# guhPLC_dimmModule_V0_1.net
KiCad netlist of a schematic drawn in EAGLE
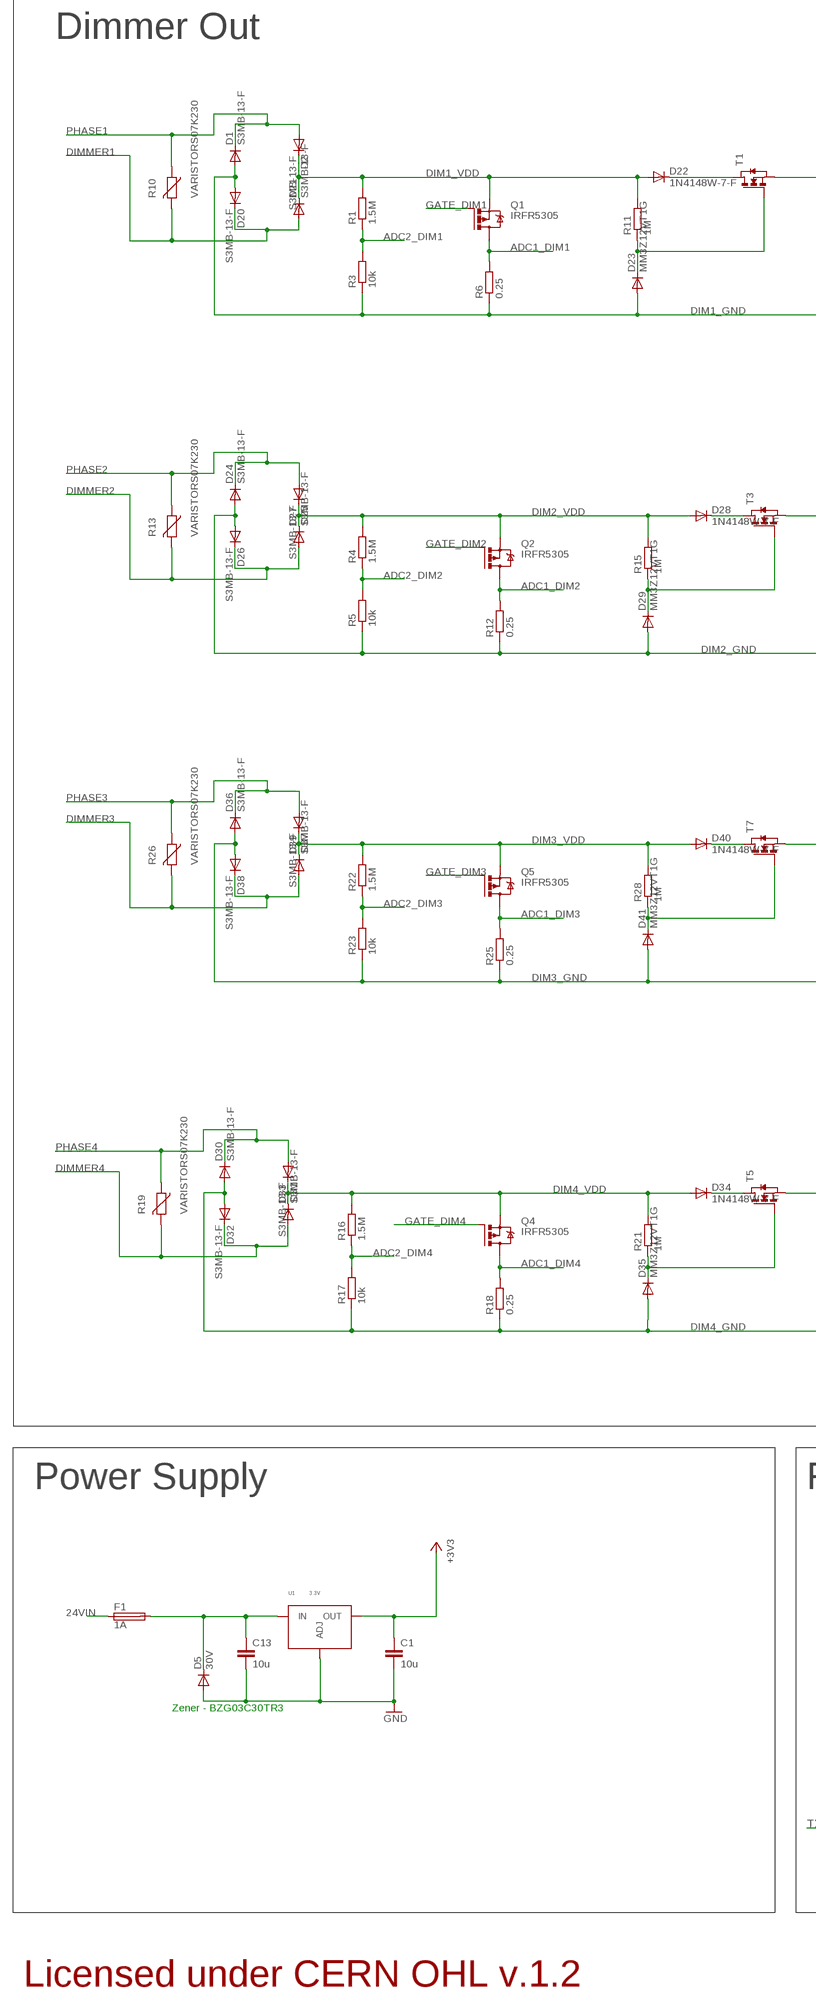
[diagram p0: schematic, sheet 1, part 1 of 2]
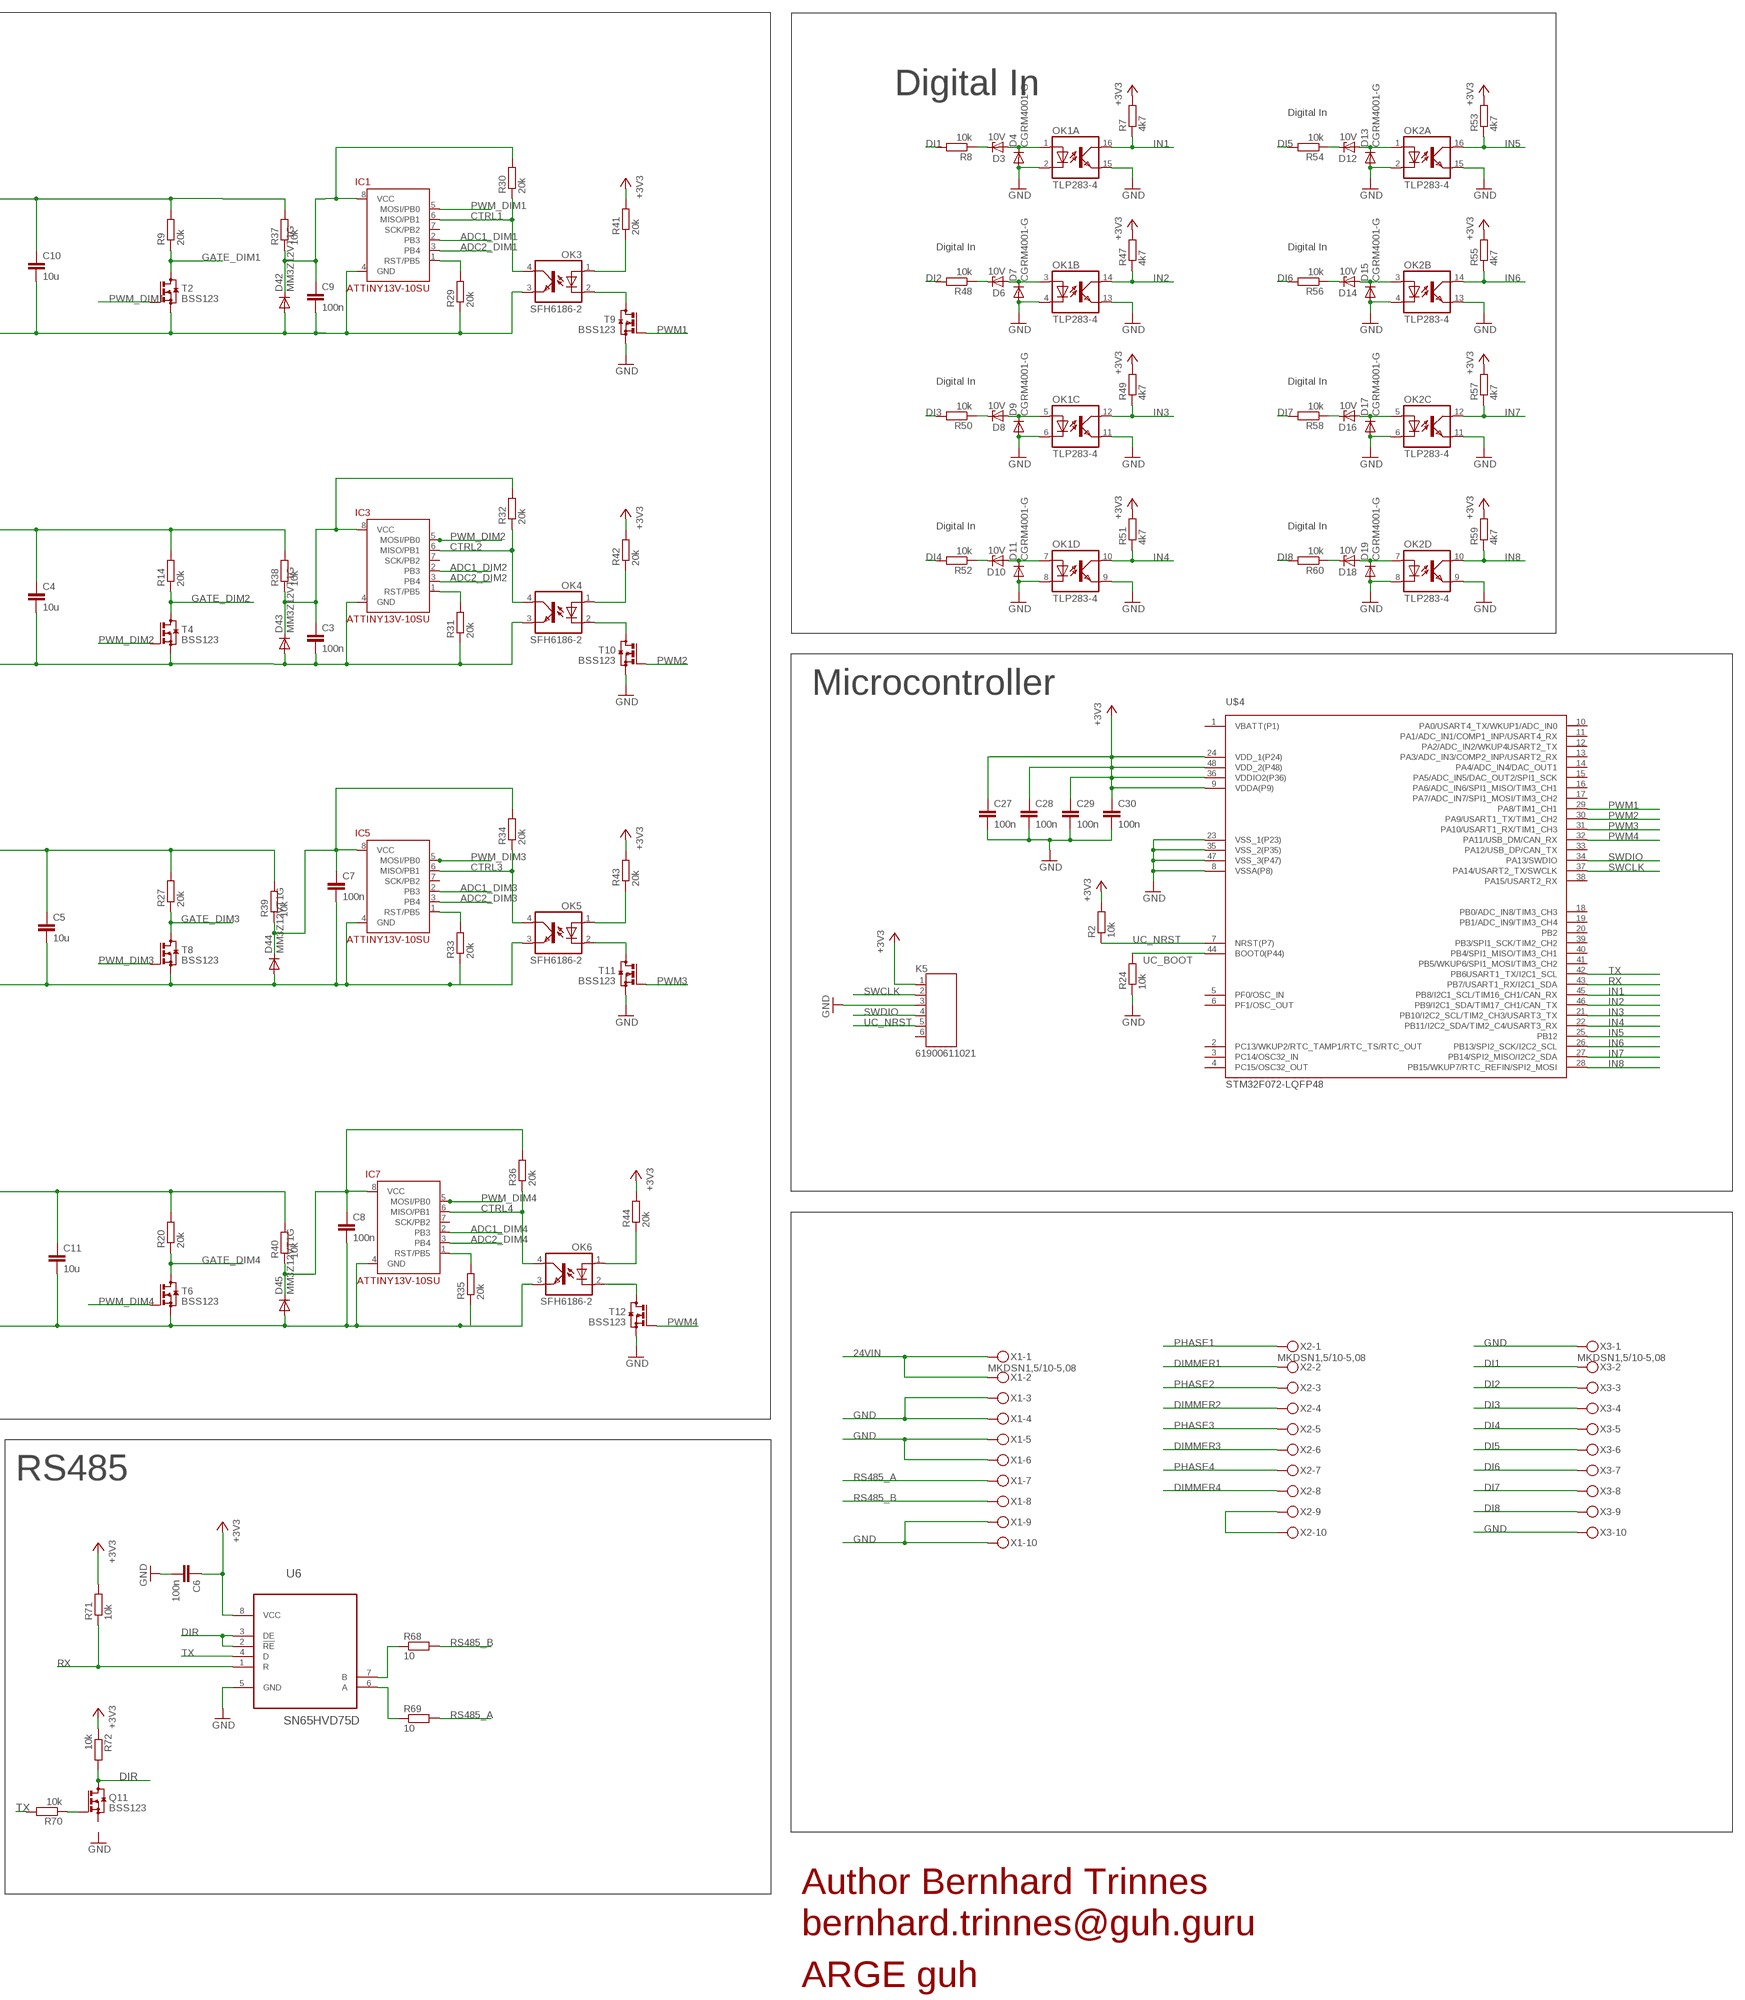
[diagram p1: schematic, sheet 1, part 2 of 2]

(export (version "E")
  (design (tool "Eeschema 10.0.6"))
  (components
    (comp (ref "C1")
      (value "10u")
      (footprint "eagle-import:C1206")
      (libsource (lib "eagle-import") (part "C-EUC1206"))
    )
    (comp (ref "C3")
      (value "100n")
      (footprint "eagle-import:C0603")
      (libsource (lib "eagle-import") (part "C-EUC0603"))
    )
    (comp (ref "C4")
      (value "10u")
      (footprint "eagle-import:C1206")
      (libsource (lib "eagle-import") (part "C-EUC1206"))
    )
    (comp (ref "C5")
      (value "10u")
      (footprint "eagle-import:C1206")
      (libsource (lib "eagle-import") (part "C-EUC1206"))
    )
    (comp (ref "C6")
      (value "100n")
      (footprint "eagle-import:C1206")
      (libsource (lib "eagle-import") (part "C-EUC1206"))
    )
    (comp (ref "C7")
      (value "100n")
      (footprint "eagle-import:C0603")
      (libsource (lib "eagle-import") (part "C-EUC0603"))
    )
    (comp (ref "C8")
      (value "100n")
      (footprint "eagle-import:C0603")
      (libsource (lib "eagle-import") (part "C-EUC0603"))
    )
    (comp (ref "C9")
      (value "100n")
      (footprint "eagle-import:C0603")
      (libsource (lib "eagle-import") (part "C-EUC0603"))
    )
    (comp (ref "C10")
      (value "10u")
      (footprint "eagle-import:C1206")
      (libsource (lib "eagle-import") (part "C-EUC1206"))
    )
    (comp (ref "C11")
      (value "10u")
      (footprint "eagle-import:C1206")
      (libsource (lib "eagle-import") (part "C-EUC1206"))
    )
    (comp (ref "C13")
      (value "10u")
      (footprint "eagle-import:C1206")
      (libsource (lib "eagle-import") (part "C-EUC1206"))
    )
    (comp (ref "C27")
      (value "100n")
      (footprint "eagle-import:C0603")
      (libsource (lib "eagle-import") (part "C-EUC0603"))
    )
    (comp (ref "C28")
      (value "100n")
      (footprint "eagle-import:C0603")
      (libsource (lib "eagle-import") (part "C-EUC0603"))
    )
    (comp (ref "C29")
      (value "100n")
      (footprint "eagle-import:C0603")
      (libsource (lib "eagle-import") (part "C-EUC0603"))
    )
    (comp (ref "C30")
      (value "100n")
      (footprint "eagle-import:C0603")
      (libsource (lib "eagle-import") (part "C-EUC0603"))
    )
    (comp (ref "D1")
      (value "S3MB-13-F")
      (footprint "eagle-import:DO214AA")
      (libsource (lib "eagle-import") (part "DIODE-DO214AA"))
    )
    (comp (ref "D2")
      (value "S3MB-13-F")
      (footprint "eagle-import:DO214AA")
      (libsource (lib "eagle-import") (part "DIODE-DO214AA"))
    )
    (comp (ref "D3")
      (value "10V")
      (footprint "eagle-import:SOD80C")
      (libsource (lib "eagle-import") (part "ZENER-DIODESOD80C"))
    )
    (comp (ref "D4")
      (value "CGRM4001-G")
      (footprint "eagle-import:SOD-123_MINI-SMA")
      (libsource (lib "eagle-import") (part "CGRM400-G1"))
    )
    (comp (ref "D5")
      (value "30V")
      (footprint "eagle-import:DO214AC")
      (libsource (lib "eagle-import") (part "DIODE-DO214AC"))
    )
    (comp (ref "D6")
      (value "10V")
      (footprint "eagle-import:SOD80C")
      (libsource (lib "eagle-import") (part "ZENER-DIODESOD80C"))
    )
    (comp (ref "D7")
      (value "CGRM4001-G")
      (footprint "eagle-import:SOD-123_MINI-SMA")
      (libsource (lib "eagle-import") (part "CGRM400-G1"))
    )
    (comp (ref "D8")
      (value "10V")
      (footprint "eagle-import:SOD80C")
      (libsource (lib "eagle-import") (part "ZENER-DIODESOD80C"))
    )
    (comp (ref "D9")
      (value "CGRM4001-G")
      (footprint "eagle-import:SOD-123_MINI-SMA")
      (libsource (lib "eagle-import") (part "CGRM400-G1"))
    )
    (comp (ref "D10")
      (value "10V")
      (footprint "eagle-import:SOD80C")
      (libsource (lib "eagle-import") (part "ZENER-DIODESOD80C"))
    )
    (comp (ref "D11")
      (value "CGRM4001-G")
      (footprint "eagle-import:SOD-123_MINI-SMA")
      (libsource (lib "eagle-import") (part "CGRM400-G1"))
    )
    (comp (ref "D12")
      (value "10V")
      (footprint "eagle-import:SOD80C")
      (libsource (lib "eagle-import") (part "ZENER-DIODESOD80C"))
    )
    (comp (ref "D13")
      (value "CGRM4001-G")
      (footprint "eagle-import:SOD-123_MINI-SMA")
      (libsource (lib "eagle-import") (part "CGRM400-G1"))
    )
    (comp (ref "D14")
      (value "10V")
      (footprint "eagle-import:SOD80C")
      (libsource (lib "eagle-import") (part "ZENER-DIODESOD80C"))
    )
    (comp (ref "D15")
      (value "CGRM4001-G")
      (footprint "eagle-import:SOD-123_MINI-SMA")
      (libsource (lib "eagle-import") (part "CGRM400-G1"))
    )
    (comp (ref "D16")
      (value "10V")
      (footprint "eagle-import:SOD80C")
      (libsource (lib "eagle-import") (part "ZENER-DIODESOD80C"))
    )
    (comp (ref "D17")
      (value "CGRM4001-G")
      (footprint "eagle-import:SOD-123_MINI-SMA")
      (libsource (lib "eagle-import") (part "CGRM400-G1"))
    )
    (comp (ref "D18")
      (value "10V")
      (footprint "eagle-import:SOD80C")
      (libsource (lib "eagle-import") (part "ZENER-DIODESOD80C"))
    )
    (comp (ref "D19")
      (value "CGRM4001-G")
      (footprint "eagle-import:SOD-123_MINI-SMA")
      (libsource (lib "eagle-import") (part "CGRM400-G1"))
    )
    (comp (ref "D20")
      (value "S3MB-13-F")
      (footprint "eagle-import:DO214AA")
      (libsource (lib "eagle-import") (part "DIODE-DO214AA"))
    )
    (comp (ref "D21")
      (value "S3MB-13-F")
      (footprint "eagle-import:DO214AA")
      (libsource (lib "eagle-import") (part "DIODE-DO214AA"))
    )
    (comp (ref "D22")
      (value "1N4148W-7-F")
      (footprint "eagle-import:SOD123")
      (libsource (lib "eagle-import") (part "DIODE-SOD123"))
    )
    (comp (ref "D23")
      (value "MM3Z12VT1G")
      (footprint "eagle-import:SOD323-W")
      (libsource (lib "eagle-import") (part "DIODE-SOD323-W"))
    )
    (comp (ref "D24")
      (value "S3MB-13-F")
      (footprint "eagle-import:DO214AA")
      (libsource (lib "eagle-import") (part "DIODE-DO214AA"))
    )
    (comp (ref "D25")
      (value "S3MB-13-F")
      (footprint "eagle-import:DO214AA")
      (libsource (lib "eagle-import") (part "DIODE-DO214AA"))
    )
    (comp (ref "D26")
      (value "S3MB-13-F")
      (footprint "eagle-import:DO214AA")
      (libsource (lib "eagle-import") (part "DIODE-DO214AA"))
    )
    (comp (ref "D27")
      (value "S3MB-13-F")
      (footprint "eagle-import:DO214AA")
      (libsource (lib "eagle-import") (part "DIODE-DO214AA"))
    )
    (comp (ref "D28")
      (value "1N4148W-7-F")
      (footprint "eagle-import:SOD123")
      (libsource (lib "eagle-import") (part "DIODE-SOD123"))
    )
    (comp (ref "D29")
      (value "MM3Z12VT1G")
      (footprint "eagle-import:SOD323-W")
      (libsource (lib "eagle-import") (part "guh_DIODE-SOD323-W"))
    )
    (comp (ref "D30")
      (value "S3MB-13-F")
      (footprint "eagle-import:DO214AA")
      (libsource (lib "eagle-import") (part "DIODE-DO214AA"))
    )
    (comp (ref "D31")
      (value "S3MB-13-F")
      (footprint "eagle-import:DO214AA")
      (libsource (lib "eagle-import") (part "DIODE-DO214AA"))
    )
    (comp (ref "D32")
      (value "S3MB-13-F")
      (footprint "eagle-import:DO214AA")
      (libsource (lib "eagle-import") (part "DIODE-DO214AA"))
    )
    (comp (ref "D33")
      (value "S3MB-13-F")
      (footprint "eagle-import:DO214AA")
      (libsource (lib "eagle-import") (part "DIODE-DO214AA"))
    )
    (comp (ref "D34")
      (value "1N4148W-7-F")
      (footprint "eagle-import:SOD123")
      (libsource (lib "eagle-import") (part "DIODE-SOD123"))
    )
    (comp (ref "D35")
      (value "MM3Z12VT1G")
      (footprint "eagle-import:SOD323-W")
      (libsource (lib "eagle-import") (part "guh_DIODE-SOD323-W"))
    )
    (comp (ref "D36")
      (value "S3MB-13-F")
      (footprint "eagle-import:DO214AA")
      (libsource (lib "eagle-import") (part "DIODE-DO214AA"))
    )
    (comp (ref "D37")
      (value "S3MB-13-F")
      (footprint "eagle-import:DO214AA")
      (libsource (lib "eagle-import") (part "DIODE-DO214AA"))
    )
    (comp (ref "D38")
      (value "S3MB-13-F")
      (footprint "eagle-import:DO214AA")
      (libsource (lib "eagle-import") (part "DIODE-DO214AA"))
    )
    (comp (ref "D39")
      (value "S3MB-13-F")
      (footprint "eagle-import:DO214AA")
      (libsource (lib "eagle-import") (part "DIODE-DO214AA"))
    )
    (comp (ref "D40")
      (value "1N4148W-7-F")
      (footprint "eagle-import:SOD123")
      (libsource (lib "eagle-import") (part "DIODE-SOD123"))
    )
    (comp (ref "D41")
      (value "MM3Z12VT1G")
      (footprint "eagle-import:SOD323-W")
      (libsource (lib "eagle-import") (part "guh_DIODE-SOD323-W"))
    )
    (comp (ref "D42")
      (value "MM3Z12VT1G")
      (footprint "eagle-import:SOD323-W")
      (libsource (lib "eagle-import") (part "DIODE-SOD323-W"))
    )
    (comp (ref "D43")
      (value "MM3Z12VT1G")
      (footprint "eagle-import:SOD323-W")
      (libsource (lib "eagle-import") (part "DIODE-SOD323-W"))
    )
    (comp (ref "D44")
      (value "MM3Z12VT1G")
      (footprint "eagle-import:SOD323-W")
      (libsource (lib "eagle-import") (part "DIODE-SOD323-W"))
    )
    (comp (ref "D45")
      (value "MM3Z12VT1G")
      (footprint "eagle-import:SOD323-W")
      (libsource (lib "eagle-import") (part "DIODE-SOD323-W"))
    )
    (comp (ref "F1")
      (value "1A")
      (footprint "eagle-import:LITTLEFUSE")
      (libsource (lib "eagle-import") (part "LITTLEFUSE"))
    )
    (comp (ref "IC1")
      (value "ATTINY13V-10SU")
      (footprint "eagle-import:SOIC8")
      (libsource (lib "eagle-import") (part "ATTINY13V-10SU"))
    )
    (comp (ref "IC3")
      (value "ATTINY13V-10SU")
      (footprint "eagle-import:SOIC8")
      (libsource (lib "eagle-import") (part "ATTINY13V-10SU"))
    )
    (comp (ref "IC5")
      (value "ATTINY13V-10SU")
      (footprint "eagle-import:SOIC8")
      (libsource (lib "eagle-import") (part "ATTINY13V-10SU"))
    )
    (comp (ref "IC7")
      (value "ATTINY13V-10SU")
      (footprint "eagle-import:SOIC8")
      (libsource (lib "eagle-import") (part "ATTINY13V-10SU"))
    )
    (comp (ref "K5")
      (value "61900611021")
      (footprint "eagle-import:61900611021")
      (libsource (lib "eagle-import") (part "61900611021"))
    )
    (comp (ref "OK1")
      (value "TLP283-4")
      (footprint "eagle-import:MINI-FLAT-16")
      (libsource (lib "eagle-import") (part "TLP283-4"))
    )
    (comp (ref "OK2")
      (value "TLP283-4")
      (footprint "eagle-import:MINI-FLAT-16")
      (libsource (lib "eagle-import") (part "TLP283-4"))
    )
    (comp (ref "OK3")
      (value "SFH6186-2")
      (footprint "eagle-import:SMD4")
      (fields (field (name "MF") "VISHAY/TELEFUNKEN"))
      (libsource (lib "eagle-import") (part "SFH618?6-2"))
    )
    (comp (ref "OK4")
      (value "SFH6186-2")
      (footprint "eagle-import:SMD4")
      (fields (field (name "MF") "VISHAY/TELEFUNKEN"))
      (libsource (lib "eagle-import") (part "SFH618?6-2"))
    )
    (comp (ref "OK5")
      (value "SFH6186-2")
      (footprint "eagle-import:SMD4")
      (fields (field (name "MF") "VISHAY/TELEFUNKEN"))
      (libsource (lib "eagle-import") (part "SFH618?6-2"))
    )
    (comp (ref "OK6")
      (value "SFH6186-2")
      (footprint "eagle-import:SMD4")
      (fields (field (name "MF") "VISHAY/TELEFUNKEN"))
      (libsource (lib "eagle-import") (part "SFH618?6-2"))
    )
    (comp (ref "Q1")
      (value "IRFR5305")
      (footprint "eagle-import:D-PAK_TO252AA")
      (libsource (lib "eagle-import") (part "IRF?5305R"))
    )
    (comp (ref "Q2")
      (value "IRFR5305")
      (footprint "eagle-import:D-PAK_TO252AA")
      (libsource (lib "eagle-import") (part "IRF?5305R"))
    )
    (comp (ref "Q4")
      (value "IRFR5305")
      (footprint "eagle-import:D-PAK_TO252AA")
      (libsource (lib "eagle-import") (part "IRF?5305R"))
    )
    (comp (ref "Q5")
      (value "IRFR5305")
      (footprint "eagle-import:D-PAK_TO252AA")
      (libsource (lib "eagle-import") (part "IRF?5305R"))
    )
    (comp (ref "Q11")
      (value "BSS123")
      (footprint "eagle-import:SOT23")
      (libsource (lib "eagle-import") (part "BSS123"))
    )
    (comp (ref "R1")
      (value "1.5M")
      (footprint "eagle-import:R1206")
      (libsource (lib "eagle-import") (part "R-EU_R1206"))
    )
    (comp (ref "R2")
      (value "10k")
      (footprint "eagle-import:R0603")
      (libsource (lib "eagle-import") (part "R-EU_R0603"))
    )
    (comp (ref "R3")
      (value "10k")
      (footprint "eagle-import:R1206")
      (libsource (lib "eagle-import") (part "R-EU_R1206"))
    )
    (comp (ref "R4")
      (value "1.5M")
      (footprint "eagle-import:M1206")
      (libsource (lib "eagle-import") (part "R-EU_M1206"))
    )
    (comp (ref "R5")
      (value "10k")
      (footprint "eagle-import:M1206")
      (libsource (lib "eagle-import") (part "R-EU_M1206"))
    )
    (comp (ref "R6")
      (value "0.25")
      (footprint "eagle-import:R1206")
      (libsource (lib "eagle-import") (part "R-EU_R1206"))
    )
    (comp (ref "R7")
      (value "4k7")
      (footprint "eagle-import:R0603")
      (libsource (lib "eagle-import") (part "R-EU_R0603"))
    )
    (comp (ref "R8")
      (value "10k")
      (footprint "eagle-import:R0805")
      (libsource (lib "eagle-import") (part "R-EU_R0805"))
    )
    (comp (ref "R9")
      (value "20k")
      (footprint "eagle-import:M1206")
      (libsource (lib "eagle-import") (part "R-EU_M1206"))
    )
    (comp (ref "R10")
      (value "VARISTORS07K230")
      (footprint "eagle-import:S07K230")
      (libsource (lib "eagle-import") (part "VARISTORS07K230"))
    )
    (comp (ref "R11")
      (value "1M")
      (footprint "eagle-import:R1206")
      (libsource (lib "eagle-import") (part "R-EU_R1206"))
    )
    (comp (ref "R12")
      (value "0.25")
      (footprint "eagle-import:M1206")
      (libsource (lib "eagle-import") (part "R-EU_M1206"))
    )
    (comp (ref "R13")
      (value "VARISTORS07K230")
      (footprint "eagle-import:S07K230")
      (libsource (lib "eagle-import") (part "VARISTORS07K230"))
    )
    (comp (ref "R14")
      (value "20k")
      (footprint "eagle-import:M1206")
      (libsource (lib "eagle-import") (part "R-EU_M1206"))
    )
    (comp (ref "R15")
      (value "1M")
      (footprint "eagle-import:M1206")
      (libsource (lib "eagle-import") (part "R-EU_M1206"))
    )
    (comp (ref "R16")
      (value "1.5M")
      (footprint "eagle-import:M1206")
      (libsource (lib "eagle-import") (part "R-EU_M1206"))
    )
    (comp (ref "R17")
      (value "10k")
      (footprint "eagle-import:M1206")
      (libsource (lib "eagle-import") (part "R-EU_M1206"))
    )
    (comp (ref "R18")
      (value "0.25")
      (footprint "eagle-import:M1206")
      (libsource (lib "eagle-import") (part "R-EU_M1206"))
    )
    (comp (ref "R19")
      (value "VARISTORS07K230")
      (footprint "eagle-import:S07K230")
      (libsource (lib "eagle-import") (part "VARISTORS07K230"))
    )
    (comp (ref "R20")
      (value "20k")
      (footprint "eagle-import:M1206")
      (libsource (lib "eagle-import") (part "R-EU_M1206"))
    )
    (comp (ref "R21")
      (value "1M")
      (footprint "eagle-import:M1206")
      (libsource (lib "eagle-import") (part "R-EU_M1206"))
    )
    (comp (ref "R22")
      (value "1.5M")
      (footprint "eagle-import:M1206")
      (libsource (lib "eagle-import") (part "R-EU_M1206"))
    )
    (comp (ref "R23")
      (value "10k")
      (footprint "eagle-import:M1206")
      (libsource (lib "eagle-import") (part "R-EU_M1206"))
    )
    (comp (ref "R24")
      (value "10k")
      (footprint "eagle-import:R0603")
      (libsource (lib "eagle-import") (part "R-EU_R0603"))
    )
    (comp (ref "R25")
      (value "0.25")
      (footprint "eagle-import:M1206")
      (libsource (lib "eagle-import") (part "R-EU_M1206"))
    )
    (comp (ref "R26")
      (value "VARISTORS07K230")
      (footprint "eagle-import:S07K230")
      (libsource (lib "eagle-import") (part "VARISTORS07K230"))
    )
    (comp (ref "R27")
      (value "20k")
      (footprint "eagle-import:M1206")
      (libsource (lib "eagle-import") (part "R-EU_M1206"))
    )
    (comp (ref "R28")
      (value "1M")
      (footprint "eagle-import:M1206")
      (libsource (lib "eagle-import") (part "R-EU_M1206"))
    )
    (comp (ref "R29")
      (value "20k")
      (footprint "eagle-import:R0603")
      (libsource (lib "eagle-import") (part "R-EU_R0603"))
    )
    (comp (ref "R30")
      (value "20k")
      (footprint "eagle-import:R0603")
      (libsource (lib "eagle-import") (part "R-EU_R0603"))
    )
    (comp (ref "R31")
      (value "20k")
      (footprint "eagle-import:R0603")
      (libsource (lib "eagle-import") (part "R-EU_R0603"))
    )
    (comp (ref "R32")
      (value "20k")
      (footprint "eagle-import:R0603")
      (libsource (lib "eagle-import") (part "R-EU_R0603"))
    )
    (comp (ref "R33")
      (value "20k")
      (footprint "eagle-import:R0603")
      (libsource (lib "eagle-import") (part "R-EU_R0603"))
    )
    (comp (ref "R34")
      (value "20k")
      (footprint "eagle-import:R0603")
      (libsource (lib "eagle-import") (part "R-EU_R0603"))
    )
    (comp (ref "R35")
      (value "20k")
      (footprint "eagle-import:R0603")
      (libsource (lib "eagle-import") (part "R-EU_R0603"))
    )
    (comp (ref "R36")
      (value "20k")
      (footprint "eagle-import:R0603")
      (libsource (lib "eagle-import") (part "R-EU_R0603"))
    )
    (comp (ref "R37")
      (value "10k")
      (footprint "eagle-import:M1206")
      (libsource (lib "eagle-import") (part "R-EU_M1206"))
    )
    (comp (ref "R38")
      (value "10k")
      (footprint "eagle-import:M1206")
      (libsource (lib "eagle-import") (part "R-EU_M1206"))
    )
    (comp (ref "R39")
      (value "10k")
      (footprint "eagle-import:M1206")
      (libsource (lib "eagle-import") (part "R-EU_M1206"))
    )
    (comp (ref "R40")
      (value "10k")
      (footprint "eagle-import:M1206")
      (libsource (lib "eagle-import") (part "R-EU_M1206"))
    )
    (comp (ref "R41")
      (value "20k")
      (footprint "eagle-import:R0603")
      (libsource (lib "eagle-import") (part "R-EU_R0603"))
    )
    (comp (ref "R42")
      (value "20k")
      (footprint "eagle-import:R0603")
      (libsource (lib "eagle-import") (part "R-EU_R0603"))
    )
    (comp (ref "R43")
      (value "20k")
      (footprint "eagle-import:R0603")
      (libsource (lib "eagle-import") (part "R-EU_R0603"))
    )
    (comp (ref "R44")
      (value "20k")
      (footprint "eagle-import:R0603")
      (libsource (lib "eagle-import") (part "R-EU_R0603"))
    )
    (comp (ref "R47")
      (value "4k7")
      (footprint "eagle-import:R0603")
      (libsource (lib "eagle-import") (part "R-EU_R0603"))
    )
    (comp (ref "R48")
      (value "10k")
      (footprint "eagle-import:R0805")
      (libsource (lib "eagle-import") (part "R-EU_R0805"))
    )
    (comp (ref "R49")
      (value "4k7")
      (footprint "eagle-import:R0603")
      (libsource (lib "eagle-import") (part "R-EU_R0603"))
    )
    (comp (ref "R50")
      (value "10k")
      (footprint "eagle-import:R0805")
      (libsource (lib "eagle-import") (part "R-EU_R0805"))
    )
    (comp (ref "R51")
      (value "4k7")
      (footprint "eagle-import:R0603")
      (libsource (lib "eagle-import") (part "R-EU_R0603"))
    )
    (comp (ref "R52")
      (value "10k")
      (footprint "eagle-import:R0805")
      (libsource (lib "eagle-import") (part "R-EU_R0805"))
    )
    (comp (ref "R53")
      (value "4k7")
      (footprint "eagle-import:R0603")
      (libsource (lib "eagle-import") (part "R-EU_R0603"))
    )
    (comp (ref "R54")
      (value "10k")
      (footprint "eagle-import:R0805")
      (libsource (lib "eagle-import") (part "R-EU_R0805"))
    )
    (comp (ref "R55")
      (value "4k7")
      (footprint "eagle-import:R0603")
      (libsource (lib "eagle-import") (part "R-EU_R0603"))
    )
    (comp (ref "R56")
      (value "10k")
      (footprint "eagle-import:R0805")
      (libsource (lib "eagle-import") (part "R-EU_R0805"))
    )
    (comp (ref "R57")
      (value "4k7")
      (footprint "eagle-import:R0603")
      (libsource (lib "eagle-import") (part "R-EU_R0603"))
    )
    (comp (ref "R58")
      (value "10k")
      (footprint "eagle-import:R0805")
      (libsource (lib "eagle-import") (part "R-EU_R0805"))
    )
    (comp (ref "R59")
      (value "4k7")
      (footprint "eagle-import:R0603")
      (libsource (lib "eagle-import") (part "R-EU_R0603"))
    )
    (comp (ref "R60")
      (value "10k")
      (footprint "eagle-import:R0805")
      (libsource (lib "eagle-import") (part "R-EU_R0805"))
    )
    (comp (ref "R68")
      (value "10")
      (footprint "eagle-import:R0603")
      (libsource (lib "eagle-import") (part "R-EU_R0603"))
    )
    (comp (ref "R69")
      (value "10")
      (footprint "eagle-import:R0603")
      (libsource (lib "eagle-import") (part "R-EU_R0603"))
    )
    (comp (ref "R70")
      (value "10k")
      (footprint "eagle-import:R0603")
      (libsource (lib "eagle-import") (part "R-EU_R0603"))
    )
    (comp (ref "R71")
      (value "10k")
      (footprint "eagle-import:R0603")
      (libsource (lib "eagle-import") (part "R-EU_R0603"))
    )
    (comp (ref "R72")
      (value "10k")
      (footprint "eagle-import:R0603")
      (libsource (lib "eagle-import") (part "R-EU_R0603"))
    )
    (comp (ref "T1")
      (value "NMOSSOT23")
      (footprint "eagle-import:SOT-23")
      (libsource (lib "eagle-import") (part "NMOSSOT23"))
    )
    (comp (ref "T2")
      (value "BSS123")
      (footprint "eagle-import:SOT23")
      (libsource (lib "eagle-import") (part "BSS123"))
    )
    (comp (ref "T3")
      (value "NMOSSOT23")
      (footprint "eagle-import:SOT-23")
      (libsource (lib "eagle-import") (part "NMOSSOT23"))
    )
    (comp (ref "T4")
      (value "BSS123")
      (footprint "eagle-import:SOT23")
      (libsource (lib "eagle-import") (part "BSS123"))
    )
    (comp (ref "T5")
      (value "NMOSSOT23")
      (footprint "eagle-import:SOT-23")
      (libsource (lib "eagle-import") (part "NMOSSOT23"))
    )
    (comp (ref "T6")
      (value "BSS123")
      (footprint "eagle-import:SOT23")
      (libsource (lib "eagle-import") (part "BSS123"))
    )
    (comp (ref "T7")
      (value "NMOSSOT23")
      (footprint "eagle-import:SOT-23")
      (libsource (lib "eagle-import") (part "NMOSSOT23"))
    )
    (comp (ref "T8")
      (value "BSS123")
      (footprint "eagle-import:SOT23")
      (libsource (lib "eagle-import") (part "BSS123"))
    )
    (comp (ref "T9")
      (value "BSS123")
      (footprint "eagle-import:SOT23")
      (libsource (lib "eagle-import") (part "BSS123"))
    )
    (comp (ref "T10")
      (value "BSS123")
      (footprint "eagle-import:SOT23")
      (libsource (lib "eagle-import") (part "BSS123"))
    )
    (comp (ref "T11")
      (value "BSS123")
      (footprint "eagle-import:SOT23")
      (libsource (lib "eagle-import") (part "BSS123"))
    )
    (comp (ref "T12")
      (value "BSS123")
      (footprint "eagle-import:SOT23")
      (libsource (lib "eagle-import") (part "BSS123"))
    )
    (comp (ref "U$4")
      (value "STM32F072-LQFP48")
      (footprint "eagle-import:LQFP48")
      (libsource (lib "eagle-import") (part "STM32F072-LQFP48"))
    )
    (comp (ref "U1")
      (value "3.3V")
      (footprint "eagle-import:TO-252-3L")
      (libsource (lib "eagle-import") (part "ADJ_VOLTAGE_REGTO-252-3L"))
    )
    (comp (ref "U6")
      (value "SN65HVD75D")
      (footprint "eagle-import:SOIC127P600X175-8N")
      (libsource (lib "eagle-import") (part "SN65HVD75D"))
    )
    (comp (ref "X1")
      (value "MKDSN1,5/10-5,08")
      (footprint "eagle-import:MKDSN1,5_10-5,08")
      (fields (field (name "MPN") "SMKDSN1,5/10-5,08"))
      (libsource (lib "eagle-import") (part "MKDSN1,5/10-5,08"))
    )
    (comp (ref "X2")
      (value "MKDSN1,5/10-5,08")
      (footprint "eagle-import:MKDSN1,5_10-5,08")
      (fields (field (name "MPN") "SMKDSN1,5/10-5,08"))
      (libsource (lib "eagle-import") (part "MKDSN1,5/10-5,08"))
    )
    (comp (ref "X3")
      (value "MKDSN1,5/10-5,08")
      (footprint "eagle-import:MKDSN1,5_10-5,08")
      (fields (field (name "MPN") "SMKDSN1,5/10-5,08"))
      (libsource (lib "eagle-import") (part "MKDSN1,5/10-5,08"))
    )
  )
  (nets
    (net (code "1") (name "+3V3") (class "Default")
      (node (ref "C1") (pin "1") (pinfunction "1_1") (pintype "passive"))
      (node (ref "C27") (pin "1") (pinfunction "1_1") (pintype "passive"))
      (node (ref "C28") (pin "1") (pinfunction "1_1") (pintype "passive"))
      (node (ref "C29") (pin "1") (pinfunction "1_1") (pintype "passive"))
      (node (ref "C30") (pin "1") (pinfunction "1_1") (pintype "passive"))
      (node (ref "C6") (pin "1") (pinfunction "1_1") (pintype "passive"))
      (node (ref "K5") (pin "1") (pinfunction "1_1") (pintype "passive"))
      (node (ref "R2") (pin "2") (pinfunction "2_2") (pintype "passive"))
      (node (ref "R41") (pin "2") (pinfunction "2_2") (pintype "passive"))
      (node (ref "R42") (pin "2") (pinfunction "2_2") (pintype "passive"))
      (node (ref "R43") (pin "2") (pinfunction "2_2") (pintype "passive"))
      (node (ref "R44") (pin "2") (pinfunction "2_2") (pintype "passive"))
      (node (ref "R47") (pin "2") (pinfunction "2_2") (pintype "passive"))
      (node (ref "R49") (pin "2") (pinfunction "2_2") (pintype "passive"))
      (node (ref "R51") (pin "2") (pinfunction "2_2") (pintype "passive"))
      (node (ref "R53") (pin "2") (pinfunction "2_2") (pintype "passive"))
      (node (ref "R55") (pin "2") (pinfunction "2_2") (pintype "passive"))
      (node (ref "R57") (pin "2") (pinfunction "2_2") (pintype "passive"))
      (node (ref "R59") (pin "2") (pinfunction "2_2") (pintype "passive"))
      (node (ref "R7") (pin "2") (pinfunction "2_2") (pintype "passive"))
      (node (ref "R71") (pin "2") (pinfunction "2_2") (pintype "passive"))
      (node (ref "R72") (pin "1") (pinfunction "1_1") (pintype "passive"))
      (node (ref "U$4") (pin "24") (pinfunction "VDD_1(P24)_24") (pintype "bidirectional"))
      (node (ref "U$4") (pin "36") (pinfunction "VDDIO2(P36)_36") (pintype "bidirectional"))
      (node (ref "U$4") (pin "48") (pinfunction "VDD_2(P48)_48") (pintype "bidirectional"))
      (node (ref "U$4") (pin "9") (pinfunction "VDDA(P9)_9") (pintype "bidirectional"))
      (node (ref "U1") (pin "PAD") (pinfunction "OUT_PAD") (pintype "bidirectional"))
      (node (ref "U6") (pin "8") (pinfunction "VCC_8") (pintype "power_in"))
    )
    (net (code "2") (name "/24VIN") (class "Default")
      (node (ref "F1") (pin "1") (pinfunction "1_1") (pintype "passive"))
      (node (ref "X1") (pin "1") (pinfunction "KL_1") (pintype "passive"))
      (node (ref "X1") (pin "2") (pinfunction "KL_2") (pintype "passive"))
    )
    (net (code "3") (name "/ADC1_DIM1") (class "Default")
      (node (ref "IC1") (pin "2") (pinfunction "PB3_2") (pintype "bidirectional"))
      (node (ref "Q1") (pin "4") (pinfunction "D_4") (pintype "passive"))
      (node (ref "R6") (pin "2") (pinfunction "2_2") (pintype "passive"))
    )
    (net (code "4") (name "/ADC1_DIM2") (class "Default")
      (node (ref "IC3") (pin "2") (pinfunction "PB3_2") (pintype "bidirectional"))
      (node (ref "Q2") (pin "4") (pinfunction "D_4") (pintype "passive"))
      (node (ref "R12") (pin "2") (pinfunction "2_2") (pintype "passive"))
    )
    (net (code "5") (name "/ADC1_DIM3") (class "Default")
      (node (ref "IC5") (pin "2") (pinfunction "PB3_2") (pintype "bidirectional"))
      (node (ref "Q5") (pin "4") (pinfunction "D_4") (pintype "passive"))
      (node (ref "R25") (pin "2") (pinfunction "2_2") (pintype "passive"))
    )
    (net (code "6") (name "/ADC1_DIM4") (class "Default")
      (node (ref "IC7") (pin "2") (pinfunction "PB3_2") (pintype "bidirectional"))
      (node (ref "Q4") (pin "4") (pinfunction "D_4") (pintype "passive"))
      (node (ref "R18") (pin "2") (pinfunction "2_2") (pintype "passive"))
    )
    (net (code "7") (name "/ADC2_DIM1") (class "Default")
      (node (ref "IC1") (pin "3") (pinfunction "PB4_3") (pintype "bidirectional"))
      (node (ref "R1") (pin "1") (pinfunction "1_1") (pintype "passive"))
      (node (ref "R3") (pin "2") (pinfunction "2_2") (pintype "passive"))
    )
    (net (code "8") (name "/ADC2_DIM2") (class "Default")
      (node (ref "IC3") (pin "3") (pinfunction "PB4_3") (pintype "bidirectional"))
      (node (ref "R4") (pin "1") (pinfunction "1_1") (pintype "passive"))
      (node (ref "R5") (pin "2") (pinfunction "2_2") (pintype "passive"))
    )
    (net (code "9") (name "/ADC2_DIM3") (class "Default")
      (node (ref "IC5") (pin "3") (pinfunction "PB4_3") (pintype "bidirectional"))
      (node (ref "R22") (pin "1") (pinfunction "1_1") (pintype "passive"))
      (node (ref "R23") (pin "2") (pinfunction "2_2") (pintype "passive"))
    )
    (net (code "10") (name "/ADC2_DIM4") (class "Default")
      (node (ref "IC7") (pin "3") (pinfunction "PB4_3") (pintype "bidirectional"))
      (node (ref "R16") (pin "1") (pinfunction "1_1") (pintype "passive"))
      (node (ref "R17") (pin "2") (pinfunction "2_2") (pintype "passive"))
    )
    (net (code "11") (name "/CTRL1") (class "Default")
      (node (ref "IC1") (pin "6") (pinfunction "MISO/PB1_6") (pintype "bidirectional"))
      (node (ref "OK3") (pin "4") (pinfunction "COL_4") (pintype "passive"))
      (node (ref "R30") (pin "1") (pinfunction "1_1") (pintype "passive"))
    )
    (net (code "12") (name "/CTRL2") (class "Default")
      (node (ref "IC3") (pin "6") (pinfunction "MISO/PB1_6") (pintype "bidirectional"))
      (node (ref "OK4") (pin "4") (pinfunction "COL_4") (pintype "passive"))
      (node (ref "R32") (pin "1") (pinfunction "1_1") (pintype "passive"))
    )
    (net (code "13") (name "/CTRL3") (class "Default")
      (node (ref "IC5") (pin "6") (pinfunction "MISO/PB1_6") (pintype "bidirectional"))
      (node (ref "OK5") (pin "4") (pinfunction "COL_4") (pintype "passive"))
      (node (ref "R34") (pin "1") (pinfunction "1_1") (pintype "passive"))
    )
    (net (code "14") (name "/CTRL4") (class "Default")
      (node (ref "IC7") (pin "6") (pinfunction "MISO/PB1_6") (pintype "bidirectional"))
      (node (ref "OK6") (pin "4") (pinfunction "COL_4") (pintype "passive"))
      (node (ref "R36") (pin "1") (pinfunction "1_1") (pintype "passive"))
    )
    (net (code "15") (name "/DI1") (class "Default")
      (node (ref "R8") (pin "2") (pinfunction "2_2") (pintype "passive"))
      (node (ref "X3") (pin "2") (pinfunction "KL_2") (pintype "passive"))
    )
    (net (code "16") (name "/DI2") (class "Default")
      (node (ref "R48") (pin "2") (pinfunction "2_2") (pintype "passive"))
      (node (ref "X3") (pin "3") (pinfunction "KL_3") (pintype "passive"))
    )
    (net (code "17") (name "/DI3") (class "Default")
      (node (ref "R50") (pin "2") (pinfunction "2_2") (pintype "passive"))
      (node (ref "X3") (pin "4") (pinfunction "KL_4") (pintype "passive"))
    )
    (net (code "18") (name "/DI4") (class "Default")
      (node (ref "R52") (pin "2") (pinfunction "2_2") (pintype "passive"))
      (node (ref "X3") (pin "5") (pinfunction "KL_5") (pintype "passive"))
    )
    (net (code "19") (name "/DI5") (class "Default")
      (node (ref "R54") (pin "2") (pinfunction "2_2") (pintype "passive"))
      (node (ref "X3") (pin "6") (pinfunction "KL_6") (pintype "passive"))
    )
    (net (code "20") (name "/DI6") (class "Default")
      (node (ref "R56") (pin "2") (pinfunction "2_2") (pintype "passive"))
      (node (ref "X3") (pin "7") (pinfunction "KL_7") (pintype "passive"))
    )
    (net (code "21") (name "/DI7") (class "Default")
      (node (ref "R58") (pin "2") (pinfunction "2_2") (pintype "passive"))
      (node (ref "X3") (pin "8") (pinfunction "KL_8") (pintype "passive"))
    )
    (net (code "22") (name "/DI8") (class "Default")
      (node (ref "R60") (pin "2") (pinfunction "2_2") (pintype "passive"))
      (node (ref "X3") (pin "9") (pinfunction "KL_9") (pintype "passive"))
    )
    (net (code "23") (name "/DIM1_GND") (class "Default")
      (node (ref "C10") (pin "2") (pinfunction "2_2") (pintype "passive"))
      (node (ref "C9") (pin "2") (pinfunction "2_2") (pintype "passive"))
      (node (ref "D1") (pin "A") (pinfunction "A_A") (pintype "passive"))
      (node (ref "D20") (pin "A") (pinfunction "A_A") (pintype "passive"))
      (node (ref "D23") (pin "A") (pinfunction "A_A") (pintype "passive"))
      (node (ref "D42") (pin "A") (pinfunction "A_A") (pintype "passive"))
      (node (ref "IC1") (pin "4") (pinfunction "GND_4") (pintype "power_in"))
      (node (ref "OK3") (pin "3") (pinfunction "EMIT_3") (pintype "passive"))
      (node (ref "R29") (pin "1") (pinfunction "1_1") (pintype "passive"))
      (node (ref "R3") (pin "1") (pinfunction "1_1") (pintype "passive"))
      (node (ref "R6") (pin "1") (pinfunction "1_1") (pintype "passive"))
      (node (ref "T2") (pin "2") (pinfunction "S_2") (pintype "passive"))
    )
    (net (code "24") (name "/DIM1_VDD") (class "Default")
      (node (ref "D2") (pin "C") (pinfunction "C_C") (pintype "passive"))
      (node (ref "D21") (pin "C") (pinfunction "C_C") (pintype "passive"))
      (node (ref "D22") (pin "A") (pinfunction "A_A") (pintype "passive"))
      (node (ref "Q1") (pin "3") (pinfunction "S_3") (pintype "passive"))
      (node (ref "R1") (pin "2") (pinfunction "2_2") (pintype "passive"))
      (node (ref "R11") (pin "2") (pinfunction "2_2") (pintype "passive"))
    )
    (net (code "25") (name "/DIM2_GND") (class "Default")
      (node (ref "C3") (pin "2") (pinfunction "2_2") (pintype "passive"))
      (node (ref "C4") (pin "2") (pinfunction "2_2") (pintype "passive"))
      (node (ref "D24") (pin "A") (pinfunction "A_A") (pintype "passive"))
      (node (ref "D26") (pin "A") (pinfunction "A_A") (pintype "passive"))
      (node (ref "D29") (pin "A") (pinfunction "A_A") (pintype "passive"))
      (node (ref "D43") (pin "A") (pinfunction "A_A") (pintype "passive"))
      (node (ref "IC3") (pin "4") (pinfunction "GND_4") (pintype "power_in"))
      (node (ref "OK4") (pin "3") (pinfunction "EMIT_3") (pintype "passive"))
      (node (ref "R12") (pin "1") (pinfunction "1_1") (pintype "passive"))
      (node (ref "R31") (pin "1") (pinfunction "1_1") (pintype "passive"))
      (node (ref "R5") (pin "1") (pinfunction "1_1") (pintype "passive"))
      (node (ref "T4") (pin "2") (pinfunction "S_2") (pintype "passive"))
    )
    (net (code "26") (name "/DIM2_VDD") (class "Default")
      (node (ref "D25") (pin "C") (pinfunction "C_C") (pintype "passive"))
      (node (ref "D27") (pin "C") (pinfunction "C_C") (pintype "passive"))
      (node (ref "D28") (pin "A") (pinfunction "A_A") (pintype "passive"))
      (node (ref "Q2") (pin "3") (pinfunction "S_3") (pintype "passive"))
      (node (ref "R15") (pin "2") (pinfunction "2_2") (pintype "passive"))
      (node (ref "R4") (pin "2") (pinfunction "2_2") (pintype "passive"))
    )
    (net (code "27") (name "/DIM3_GND") (class "Default")
      (node (ref "C5") (pin "2") (pinfunction "2_2") (pintype "passive"))
      (node (ref "C7") (pin "2") (pinfunction "2_2") (pintype "passive"))
      (node (ref "D36") (pin "A") (pinfunction "A_A") (pintype "passive"))
      (node (ref "D38") (pin "A") (pinfunction "A_A") (pintype "passive"))
      (node (ref "D41") (pin "A") (pinfunction "A_A") (pintype "passive"))
      (node (ref "D44") (pin "A") (pinfunction "A_A") (pintype "passive"))
      (node (ref "IC5") (pin "4") (pinfunction "GND_4") (pintype "power_in"))
      (node (ref "OK5") (pin "3") (pinfunction "EMIT_3") (pintype "passive"))
      (node (ref "R23") (pin "1") (pinfunction "1_1") (pintype "passive"))
      (node (ref "R25") (pin "1") (pinfunction "1_1") (pintype "passive"))
      (node (ref "R33") (pin "1") (pinfunction "1_1") (pintype "passive"))
      (node (ref "T8") (pin "2") (pinfunction "S_2") (pintype "passive"))
    )
    (net (code "28") (name "/DIM3_VDD") (class "Default")
      (node (ref "D37") (pin "C") (pinfunction "C_C") (pintype "passive"))
      (node (ref "D39") (pin "C") (pinfunction "C_C") (pintype "passive"))
      (node (ref "D40") (pin "A") (pinfunction "A_A") (pintype "passive"))
      (node (ref "Q5") (pin "3") (pinfunction "S_3") (pintype "passive"))
      (node (ref "R22") (pin "2") (pinfunction "2_2") (pintype "passive"))
      (node (ref "R28") (pin "2") (pinfunction "2_2") (pintype "passive"))
    )
    (net (code "29") (name "/DIM4_GND") (class "Default")
      (node (ref "C11") (pin "2") (pinfunction "2_2") (pintype "passive"))
      (node (ref "C8") (pin "2") (pinfunction "2_2") (pintype "passive"))
      (node (ref "D30") (pin "A") (pinfunction "A_A") (pintype "passive"))
      (node (ref "D32") (pin "A") (pinfunction "A_A") (pintype "passive"))
      (node (ref "D35") (pin "A") (pinfunction "A_A") (pintype "passive"))
      (node (ref "D45") (pin "A") (pinfunction "A_A") (pintype "passive"))
      (node (ref "IC7") (pin "4") (pinfunction "GND_4") (pintype "power_in"))
      (node (ref "OK6") (pin "3") (pinfunction "EMIT_3") (pintype "passive"))
      (node (ref "R17") (pin "1") (pinfunction "1_1") (pintype "passive"))
      (node (ref "R18") (pin "1") (pinfunction "1_1") (pintype "passive"))
      (node (ref "R35") (pin "1") (pinfunction "1_1") (pintype "passive"))
      (node (ref "T6") (pin "2") (pinfunction "S_2") (pintype "passive"))
    )
    (net (code "30") (name "/DIM4_VDD") (class "Default")
      (node (ref "D31") (pin "C") (pinfunction "C_C") (pintype "passive"))
      (node (ref "D33") (pin "C") (pinfunction "C_C") (pintype "passive"))
      (node (ref "D34") (pin "A") (pinfunction "A_A") (pintype "passive"))
      (node (ref "Q4") (pin "3") (pinfunction "S_3") (pintype "passive"))
      (node (ref "R16") (pin "2") (pinfunction "2_2") (pintype "passive"))
      (node (ref "R21") (pin "2") (pinfunction "2_2") (pintype "passive"))
    )
    (net (code "31") (name "/DIMMER1") (class "Default")
      (node (ref "D20") (pin "C") (pinfunction "C_C") (pintype "passive"))
      (node (ref "D21") (pin "A") (pinfunction "A_A") (pintype "passive"))
      (node (ref "R10") (pin "2") (pinfunction "2_2") (pintype "passive"))
      (node (ref "X2") (pin "2") (pinfunction "KL_2") (pintype "passive"))
    )
    (net (code "32") (name "/DIMMER2") (class "Default")
      (node (ref "D26") (pin "C") (pinfunction "C_C") (pintype "passive"))
      (node (ref "D27") (pin "A") (pinfunction "A_A") (pintype "passive"))
      (node (ref "R13") (pin "2") (pinfunction "2_2") (pintype "passive"))
      (node (ref "X2") (pin "4") (pinfunction "KL_4") (pintype "passive"))
    )
    (net (code "33") (name "/DIMMER3") (class "Default")
      (node (ref "D38") (pin "C") (pinfunction "C_C") (pintype "passive"))
      (node (ref "D39") (pin "A") (pinfunction "A_A") (pintype "passive"))
      (node (ref "R26") (pin "2") (pinfunction "2_2") (pintype "passive"))
      (node (ref "X2") (pin "6") (pinfunction "KL_6") (pintype "passive"))
    )
    (net (code "34") (name "/DIMMER4") (class "Default")
      (node (ref "D32") (pin "C") (pinfunction "C_C") (pintype "passive"))
      (node (ref "D33") (pin "A") (pinfunction "A_A") (pintype "passive"))
      (node (ref "R19") (pin "2") (pinfunction "2_2") (pintype "passive"))
      (node (ref "X2") (pin "8") (pinfunction "KL_8") (pintype "passive"))
    )
    (net (code "35") (name "/DIR") (class "Default")
      (node (ref "Q11") (pin "3") (pinfunction "D_3") (pintype "passive"))
      (node (ref "R72") (pin "2") (pinfunction "2_2") (pintype "passive"))
      (node (ref "U6") (pin "2") (pinfunction "~{RE}_2") (pintype "input"))
      (node (ref "U6") (pin "3") (pinfunction "DE_3") (pintype "input"))
    )
    (net (code "36") (name "/GATE_DIM1") (class "Default")
      (node (ref "Q1") (pin "1") (pinfunction "G_1") (pintype "passive"))
      (node (ref "R9") (pin "1") (pinfunction "1_1") (pintype "passive"))
      (node (ref "T2") (pin "3") (pinfunction "D_3") (pintype "passive"))
    )
    (net (code "37") (name "/GATE_DIM2") (class "Default")
      (node (ref "Q2") (pin "1") (pinfunction "G_1") (pintype "passive"))
      (node (ref "R14") (pin "1") (pinfunction "1_1") (pintype "passive"))
      (node (ref "T4") (pin "3") (pinfunction "D_3") (pintype "passive"))
    )
    (net (code "38") (name "/GATE_DIM3") (class "Default")
      (node (ref "Q5") (pin "1") (pinfunction "G_1") (pintype "passive"))
      (node (ref "R27") (pin "1") (pinfunction "1_1") (pintype "passive"))
      (node (ref "T8") (pin "3") (pinfunction "D_3") (pintype "passive"))
    )
    (net (code "39") (name "/GATE_DIM4") (class "Default")
      (node (ref "Q4") (pin "1") (pinfunction "G_1") (pintype "passive"))
      (node (ref "R20") (pin "1") (pinfunction "1_1") (pintype "passive"))
      (node (ref "T6") (pin "3") (pinfunction "D_3") (pintype "passive"))
    )
    (net (code "40") (name "/IN1") (class "Default")
      (node (ref "OK1") (pin "16") (pinfunction "COL_16") (pintype "passive"))
      (node (ref "R7") (pin "1") (pinfunction "1_1") (pintype "passive"))
      (node (ref "U$4") (pin "45") (pinfunction "PB8/I2C1_SCL/TIM16_CH1/CAN_RX_45") (pintype "bidirectional"))
    )
    (net (code "41") (name "/IN2") (class "Default")
      (node (ref "OK1") (pin "14") (pinfunction "COL_14") (pintype "passive"))
      (node (ref "R47") (pin "1") (pinfunction "1_1") (pintype "passive"))
      (node (ref "U$4") (pin "46") (pinfunction "PB9/I2C1_SDA/TIM17_CH1/CAN_TX_46") (pintype "bidirectional"))
    )
    (net (code "42") (name "/IN3") (class "Default")
      (node (ref "OK1") (pin "12") (pinfunction "COL_12") (pintype "passive"))
      (node (ref "R49") (pin "1") (pinfunction "1_1") (pintype "passive"))
      (node (ref "U$4") (pin "21") (pinfunction "PB10/I2C2_SCL/TIM2_CH3/USART3_TX_21") (pintype "bidirectional"))
    )
    (net (code "43") (name "/IN4") (class "Default")
      (node (ref "OK1") (pin "10") (pinfunction "COL_10") (pintype "passive"))
      (node (ref "R51") (pin "1") (pinfunction "1_1") (pintype "passive"))
      (node (ref "U$4") (pin "22") (pinfunction "PB11/I2C2_SDA/TIM2_C4/USART3_RX_22") (pintype "bidirectional"))
    )
    (net (code "44") (name "/IN5") (class "Default")
      (node (ref "OK2") (pin "16") (pinfunction "COL_16") (pintype "passive"))
      (node (ref "R53") (pin "1") (pinfunction "1_1") (pintype "passive"))
      (node (ref "U$4") (pin "25") (pinfunction "PB12_25") (pintype "bidirectional"))
    )
    (net (code "45") (name "/IN6") (class "Default")
      (node (ref "OK2") (pin "14") (pinfunction "COL_14") (pintype "passive"))
      (node (ref "R55") (pin "1") (pinfunction "1_1") (pintype "passive"))
      (node (ref "U$4") (pin "26") (pinfunction "PB13/SPI2_SCK/I2C2_SCL_26") (pintype "bidirectional"))
    )
    (net (code "46") (name "/IN7") (class "Default")
      (node (ref "OK2") (pin "12") (pinfunction "COL_12") (pintype "passive"))
      (node (ref "R57") (pin "1") (pinfunction "1_1") (pintype "passive"))
      (node (ref "U$4") (pin "27") (pinfunction "PB14/SPI2_MISO/I2C2_SDA_27") (pintype "bidirectional"))
    )
    (net (code "47") (name "/IN8") (class "Default")
      (node (ref "OK2") (pin "10") (pinfunction "COL_10") (pintype "passive"))
      (node (ref "R59") (pin "1") (pinfunction "1_1") (pintype "passive"))
      (node (ref "U$4") (pin "28") (pinfunction "PB15/WKUP7/RTC_REFIN/SPI2_MOSI_28") (pintype "bidirectional"))
    )
    (net (code "48") (name "/PHASE1") (class "Default")
      (node (ref "D1") (pin "C") (pinfunction "C_C") (pintype "passive"))
      (node (ref "D2") (pin "A") (pinfunction "A_A") (pintype "passive"))
      (node (ref "R10") (pin "1") (pinfunction "1_1") (pintype "passive"))
      (node (ref "X2") (pin "1") (pinfunction "KL_1") (pintype "passive"))
    )
    (net (code "49") (name "/PHASE2") (class "Default")
      (node (ref "D24") (pin "C") (pinfunction "C_C") (pintype "passive"))
      (node (ref "D25") (pin "A") (pinfunction "A_A") (pintype "passive"))
      (node (ref "R13") (pin "1") (pinfunction "1_1") (pintype "passive"))
      (node (ref "X2") (pin "3") (pinfunction "KL_3") (pintype "passive"))
    )
    (net (code "50") (name "/PHASE3") (class "Default")
      (node (ref "D36") (pin "C") (pinfunction "C_C") (pintype "passive"))
      (node (ref "D37") (pin "A") (pinfunction "A_A") (pintype "passive"))
      (node (ref "R26") (pin "1") (pinfunction "1_1") (pintype "passive"))
      (node (ref "X2") (pin "5") (pinfunction "KL_5") (pintype "passive"))
    )
    (net (code "51") (name "/PHASE4") (class "Default")
      (node (ref "D30") (pin "C") (pinfunction "C_C") (pintype "passive"))
      (node (ref "D31") (pin "A") (pinfunction "A_A") (pintype "passive"))
      (node (ref "R19") (pin "1") (pinfunction "1_1") (pintype "passive"))
      (node (ref "X2") (pin "7") (pinfunction "KL_7") (pintype "passive"))
    )
    (net (code "52") (name "/PWM1") (class "Default")
      (node (ref "T9") (pin "1") (pinfunction "G_1") (pintype "passive"))
      (node (ref "U$4") (pin "29") (pinfunction "PA8/TIM1_CH1_29") (pintype "bidirectional"))
    )
    (net (code "53") (name "/PWM2") (class "Default")
      (node (ref "T10") (pin "1") (pinfunction "G_1") (pintype "passive"))
      (node (ref "U$4") (pin "30") (pinfunction "PA9/USART1_TX/TIM1_CH2_30") (pintype "bidirectional"))
    )
    (net (code "54") (name "/PWM3") (class "Default")
      (node (ref "T11") (pin "1") (pinfunction "G_1") (pintype "passive"))
      (node (ref "U$4") (pin "31") (pinfunction "PA10/USART1_RX/TIM1_CH3_31") (pintype "bidirectional"))
    )
    (net (code "55") (name "/PWM4") (class "Default")
      (node (ref "T12") (pin "1") (pinfunction "G_1") (pintype "passive"))
      (node (ref "U$4") (pin "32") (pinfunction "PA11/USB_DM/CAN_RX_32") (pintype "bidirectional"))
    )
    (net (code "56") (name "/PWM_DIM1") (class "Default")
      (node (ref "IC1") (pin "5") (pinfunction "MOSI/PB0_5") (pintype "bidirectional"))
      (node (ref "T2") (pin "1") (pinfunction "G_1") (pintype "passive"))
    )
    (net (code "57") (name "/PWM_DIM2") (class "Default")
      (node (ref "IC3") (pin "5") (pinfunction "MOSI/PB0_5") (pintype "bidirectional"))
      (node (ref "T4") (pin "1") (pinfunction "G_1") (pintype "passive"))
    )
    (net (code "58") (name "/PWM_DIM3") (class "Default")
      (node (ref "IC5") (pin "5") (pinfunction "MOSI/PB0_5") (pintype "bidirectional"))
      (node (ref "T8") (pin "1") (pinfunction "G_1") (pintype "passive"))
    )
    (net (code "59") (name "/PWM_DIM4") (class "Default")
      (node (ref "IC7") (pin "5") (pinfunction "MOSI/PB0_5") (pintype "bidirectional"))
      (node (ref "T6") (pin "1") (pinfunction "G_1") (pintype "passive"))
    )
    (net (code "60") (name "/RS485_A") (class "Default")
      (node (ref "R69") (pin "2") (pinfunction "2_2") (pintype "passive"))
      (node (ref "X1") (pin "7") (pinfunction "KL_7") (pintype "passive"))
    )
    (net (code "61") (name "/RS485_B") (class "Default")
      (node (ref "R68") (pin "2") (pinfunction "2_2") (pintype "passive"))
      (node (ref "X1") (pin "8") (pinfunction "KL_8") (pintype "passive"))
    )
    (net (code "62") (name "/RX") (class "Default")
      (node (ref "R71") (pin "1") (pinfunction "1_1") (pintype "passive"))
      (node (ref "U$4") (pin "43") (pinfunction "PB7/USART1_RX/I2C1_SDA_43") (pintype "bidirectional"))
      (node (ref "U6") (pin "1") (pinfunction "R_1") (pintype "input"))
    )
    (net (code "63") (name "/SWCLK") (class "Default")
      (node (ref "K5") (pin "2") (pinfunction "2_2") (pintype "passive"))
      (node (ref "U$4") (pin "37") (pinfunction "PA14/USART2_TX/SWCLK_37") (pintype "bidirectional"))
    )
    (net (code "64") (name "/SWDIO") (class "Default")
      (node (ref "K5") (pin "4") (pinfunction "4_4") (pintype "passive"))
      (node (ref "U$4") (pin "34") (pinfunction "PA13/SWDIO_34") (pintype "bidirectional"))
    )
    (net (code "65") (name "/TX") (class "Default")
      (node (ref "R70") (pin "2") (pinfunction "2_2") (pintype "passive"))
      (node (ref "U$4") (pin "42") (pinfunction "PB6USART1_TX/I2C1_SCL_42") (pintype "bidirectional"))
      (node (ref "U6") (pin "4") (pinfunction "D_4") (pintype "input"))
    )
    (net (code "66") (name "/UC_BOOT") (class "Default")
      (node (ref "R24") (pin "2") (pinfunction "2_2") (pintype "passive"))
      (node (ref "U$4") (pin "44") (pinfunction "BOOT0(P44)_44") (pintype "bidirectional"))
    )
    (net (code "67") (name "/UC_NRST") (class "Default")
      (node (ref "K5") (pin "5") (pinfunction "5_5") (pintype "passive"))
      (node (ref "R2") (pin "1") (pinfunction "1_1") (pintype "passive"))
      (node (ref "U$4") (pin "7") (pinfunction "NRST(P7)_7") (pintype "bidirectional"))
    )
    (net (code "68") (name "GND") (class "Default")
      (node (ref "C1") (pin "2") (pinfunction "2_2") (pintype "passive"))
      (node (ref "C13") (pin "2") (pinfunction "2_2") (pintype "passive"))
      (node (ref "C27") (pin "2") (pinfunction "2_2") (pintype "passive"))
      (node (ref "C28") (pin "2") (pinfunction "2_2") (pintype "passive"))
      (node (ref "C29") (pin "2") (pinfunction "2_2") (pintype "passive"))
      (node (ref "C30") (pin "2") (pinfunction "2_2") (pintype "passive"))
      (node (ref "C6") (pin "2") (pinfunction "2_2") (pintype "passive"))
      (node (ref "D11") (pin "A") (pinfunction "A_A") (pintype "passive"))
      (node (ref "D13") (pin "A") (pinfunction "A_A") (pintype "passive"))
      (node (ref "D15") (pin "A") (pinfunction "A_A") (pintype "passive"))
      (node (ref "D17") (pin "A") (pinfunction "A_A") (pintype "passive"))
      (node (ref "D19") (pin "A") (pinfunction "A_A") (pintype "passive"))
      (node (ref "D4") (pin "A") (pinfunction "A_A") (pintype "passive"))
      (node (ref "D5") (pin "A") (pinfunction "A_A") (pintype "passive"))
      (node (ref "D7") (pin "A") (pinfunction "A_A") (pintype "passive"))
      (node (ref "D9") (pin "A") (pinfunction "A_A") (pintype "passive"))
      (node (ref "K5") (pin "3") (pinfunction "3_3") (pintype "passive"))
      (node (ref "OK1") (pin "11") (pinfunction "EMIT_11") (pintype "passive"))
      (node (ref "OK1") (pin "13") (pinfunction "EMIT_13") (pintype "passive"))
      (node (ref "OK1") (pin "15") (pinfunction "EMIT_15") (pintype "passive"))
      (node (ref "OK1") (pin "2") (pinfunction "C_2") (pintype "passive"))
      (node (ref "OK1") (pin "4") (pinfunction "C_4") (pintype "passive"))
      (node (ref "OK1") (pin "6") (pinfunction "C_6") (pintype "passive"))
      (node (ref "OK1") (pin "8") (pinfunction "C_8") (pintype "passive"))
      (node (ref "OK1") (pin "9") (pinfunction "EMIT_9") (pintype "passive"))
      (node (ref "OK2") (pin "11") (pinfunction "EMIT_11") (pintype "passive"))
      (node (ref "OK2") (pin "13") (pinfunction "EMIT_13") (pintype "passive"))
      (node (ref "OK2") (pin "15") (pinfunction "EMIT_15") (pintype "passive"))
      (node (ref "OK2") (pin "2") (pinfunction "C_2") (pintype "passive"))
      (node (ref "OK2") (pin "4") (pinfunction "C_4") (pintype "passive"))
      (node (ref "OK2") (pin "6") (pinfunction "C_6") (pintype "passive"))
      (node (ref "OK2") (pin "8") (pinfunction "C_8") (pintype "passive"))
      (node (ref "OK2") (pin "9") (pinfunction "EMIT_9") (pintype "passive"))
      (node (ref "R24") (pin "1") (pinfunction "1_1") (pintype "passive"))
      (node (ref "T10") (pin "2") (pinfunction "S_2") (pintype "passive"))
      (node (ref "T11") (pin "2") (pinfunction "S_2") (pintype "passive"))
      (node (ref "T12") (pin "2") (pinfunction "S_2") (pintype "passive"))
      (node (ref "T9") (pin "2") (pinfunction "S_2") (pintype "passive"))
      (node (ref "U$4") (pin "23") (pinfunction "VSS_1(P23)_23") (pintype "bidirectional"))
      (node (ref "U$4") (pin "35") (pinfunction "VSS_2(P35)_35") (pintype "bidirectional"))
      (node (ref "U$4") (pin "47") (pinfunction "VSS_3(P47)_47") (pintype "bidirectional"))
      (node (ref "U$4") (pin "8") (pinfunction "VSSA(P8)_8") (pintype "bidirectional"))
      (node (ref "U1") (pin "1") (pinfunction "ADJ_1") (pintype "bidirectional"))
      (node (ref "U6") (pin "5") (pinfunction "GND_5") (pintype "passive"))
      (node (ref "X1") (pin "10") (pinfunction "KL_10") (pintype "passive"))
      (node (ref "X1") (pin "3") (pinfunction "KL_3") (pintype "passive"))
      (node (ref "X1") (pin "4") (pinfunction "KL_4") (pintype "passive"))
      (node (ref "X1") (pin "5") (pinfunction "KL_5") (pintype "passive"))
      (node (ref "X1") (pin "6") (pinfunction "KL_6") (pintype "passive"))
      (node (ref "X1") (pin "9") (pinfunction "KL_9") (pintype "passive"))
      (node (ref "X3") (pin "1") (pinfunction "KL_1") (pintype "passive"))
      (node (ref "X3") (pin "10") (pinfunction "KL_10") (pintype "passive"))
    )
    (net (code "69") (name "Net-(D3-PadC)") (class "Default")
      (node (ref "D3") (pin "C") (pinfunction "C_C") (pintype "passive"))
      (node (ref "R8") (pin "1") (pinfunction "1_1") (pintype "passive"))
    )
    (net (code "70") (name "Net-(D6-PadC)") (class "Default")
      (node (ref "D6") (pin "C") (pinfunction "C_C") (pintype "passive"))
      (node (ref "R48") (pin "1") (pinfunction "1_1") (pintype "passive"))
    )
    (net (code "71") (name "Net-(D8-PadC)") (class "Default")
      (node (ref "D8") (pin "C") (pinfunction "C_C") (pintype "passive"))
      (node (ref "R50") (pin "1") (pinfunction "1_1") (pintype "passive"))
    )
    (net (code "72") (name "Net-(D10-PadC)") (class "Default")
      (node (ref "D10") (pin "C") (pinfunction "C_C") (pintype "passive"))
      (node (ref "R52") (pin "1") (pinfunction "1_1") (pintype "passive"))
    )
    (net (code "73") (name "Net-(D12-PadC)") (class "Default")
      (node (ref "D12") (pin "C") (pinfunction "C_C") (pintype "passive"))
      (node (ref "R54") (pin "1") (pinfunction "1_1") (pintype "passive"))
    )
    (net (code "74") (name "Net-(D14-PadC)") (class "Default")
      (node (ref "D14") (pin "C") (pinfunction "C_C") (pintype "passive"))
      (node (ref "R56") (pin "1") (pinfunction "1_1") (pintype "passive"))
    )
    (net (code "75") (name "Net-(D16-PadC)") (class "Default")
      (node (ref "D16") (pin "C") (pinfunction "C_C") (pintype "passive"))
      (node (ref "R58") (pin "1") (pinfunction "1_1") (pintype "passive"))
    )
    (net (code "76") (name "Net-(D18-PadC)") (class "Default")
      (node (ref "D18") (pin "C") (pinfunction "C_C") (pintype "passive"))
      (node (ref "R60") (pin "1") (pinfunction "1_1") (pintype "passive"))
    )
    (net (code "77") (name "Net-(IC1-RST{slash}PB5)") (class "Default")
      (node (ref "IC1") (pin "1") (pinfunction "RST/PB5_1") (pintype "bidirectional"))
      (node (ref "R29") (pin "2") (pinfunction "2_2") (pintype "passive"))
    )
    (net (code "78") (name "Net-(IC1-VCC)") (class "Default")
      (node (ref "C9") (pin "1") (pinfunction "1_1") (pintype "passive"))
      (node (ref "D42") (pin "C") (pinfunction "C_C") (pintype "passive"))
      (node (ref "IC1") (pin "8") (pinfunction "VCC_8") (pintype "power_in"))
      (node (ref "R30") (pin "2") (pinfunction "2_2") (pintype "passive"))
      (node (ref "R37") (pin "1") (pinfunction "1_1") (pintype "passive"))
    )
    (net (code "79") (name "Net-(IC3-RST{slash}PB5)") (class "Default")
      (node (ref "IC3") (pin "1") (pinfunction "RST/PB5_1") (pintype "bidirectional"))
      (node (ref "R31") (pin "2") (pinfunction "2_2") (pintype "passive"))
    )
    (net (code "80") (name "Net-(IC3-VCC)") (class "Default")
      (node (ref "C3") (pin "1") (pinfunction "1_1") (pintype "passive"))
      (node (ref "D43") (pin "C") (pinfunction "C_C") (pintype "passive"))
      (node (ref "IC3") (pin "8") (pinfunction "VCC_8") (pintype "power_in"))
      (node (ref "R32") (pin "2") (pinfunction "2_2") (pintype "passive"))
      (node (ref "R38") (pin "1") (pinfunction "1_1") (pintype "passive"))
    )
    (net (code "81") (name "Net-(IC5-RST{slash}PB5)") (class "Default")
      (node (ref "IC5") (pin "1") (pinfunction "RST/PB5_1") (pintype "bidirectional"))
      (node (ref "R33") (pin "2") (pinfunction "2_2") (pintype "passive"))
    )
    (net (code "82") (name "Net-(IC5-VCC)") (class "Default")
      (node (ref "C7") (pin "1") (pinfunction "1_1") (pintype "passive"))
      (node (ref "D44") (pin "C") (pinfunction "C_C") (pintype "passive"))
      (node (ref "IC5") (pin "8") (pinfunction "VCC_8") (pintype "power_in"))
      (node (ref "R34") (pin "2") (pinfunction "2_2") (pintype "passive"))
      (node (ref "R39") (pin "1") (pinfunction "1_1") (pintype "passive"))
    )
    (net (code "83") (name "Net-(IC7-RST{slash}PB5)") (class "Default")
      (node (ref "IC7") (pin "1") (pinfunction "RST/PB5_1") (pintype "bidirectional"))
      (node (ref "R35") (pin "2") (pinfunction "2_2") (pintype "passive"))
    )
    (net (code "84") (name "Net-(IC7-VCC)") (class "Default")
      (node (ref "C8") (pin "1") (pinfunction "1_1") (pintype "passive"))
      (node (ref "D45") (pin "C") (pinfunction "C_C") (pintype "passive"))
      (node (ref "IC7") (pin "8") (pinfunction "VCC_8") (pintype "power_in"))
      (node (ref "R36") (pin "2") (pinfunction "2_2") (pintype "passive"))
      (node (ref "R40") (pin "1") (pinfunction "1_1") (pintype "passive"))
    )
    (net (code "85") (name "Net-(OK1A-A)") (class "Default")
      (node (ref "D3") (pin "A") (pinfunction "A_A") (pintype "passive"))
      (node (ref "D4") (pin "C") (pinfunction "C_C") (pintype "passive"))
      (node (ref "OK1") (pin "1") (pinfunction "A_1") (pintype "passive"))
    )
    (net (code "86") (name "Net-(OK1B-A)") (class "Default")
      (node (ref "D6") (pin "A") (pinfunction "A_A") (pintype "passive"))
      (node (ref "D7") (pin "C") (pinfunction "C_C") (pintype "passive"))
      (node (ref "OK1") (pin "3") (pinfunction "A_3") (pintype "passive"))
    )
    (net (code "87") (name "Net-(OK1C-A)") (class "Default")
      (node (ref "D8") (pin "A") (pinfunction "A_A") (pintype "passive"))
      (node (ref "D9") (pin "C") (pinfunction "C_C") (pintype "passive"))
      (node (ref "OK1") (pin "5") (pinfunction "A_5") (pintype "passive"))
    )
    (net (code "88") (name "Net-(OK1D-A)") (class "Default")
      (node (ref "D10") (pin "A") (pinfunction "A_A") (pintype "passive"))
      (node (ref "D11") (pin "C") (pinfunction "C_C") (pintype "passive"))
      (node (ref "OK1") (pin "7") (pinfunction "A_7") (pintype "passive"))
    )
    (net (code "89") (name "Net-(OK2A-A)") (class "Default")
      (node (ref "D12") (pin "A") (pinfunction "A_A") (pintype "passive"))
      (node (ref "D13") (pin "C") (pinfunction "C_C") (pintype "passive"))
      (node (ref "OK2") (pin "1") (pinfunction "A_1") (pintype "passive"))
    )
    (net (code "90") (name "Net-(OK2B-A)") (class "Default")
      (node (ref "D14") (pin "A") (pinfunction "A_A") (pintype "passive"))
      (node (ref "D15") (pin "C") (pinfunction "C_C") (pintype "passive"))
      (node (ref "OK2") (pin "3") (pinfunction "A_3") (pintype "passive"))
    )
    (net (code "91") (name "Net-(OK2C-A)") (class "Default")
      (node (ref "D16") (pin "A") (pinfunction "A_A") (pintype "passive"))
      (node (ref "D17") (pin "C") (pinfunction "C_C") (pintype "passive"))
      (node (ref "OK2") (pin "5") (pinfunction "A_5") (pintype "passive"))
    )
    (net (code "92") (name "Net-(OK2D-A)") (class "Default")
      (node (ref "D18") (pin "A") (pinfunction "A_A") (pintype "passive"))
      (node (ref "D19") (pin "C") (pinfunction "C_C") (pintype "passive"))
      (node (ref "OK2") (pin "7") (pinfunction "A_7") (pintype "passive"))
    )
    (net (code "93") (name "Net-(OK3-A)") (class "Default")
      (node (ref "OK3") (pin "1") (pinfunction "A_1") (pintype "passive"))
      (node (ref "R41") (pin "1") (pinfunction "1_1") (pintype "passive"))
    )
    (net (code "94") (name "Net-(OK3-C)") (class "Default")
      (node (ref "OK3") (pin "2") (pinfunction "C_2") (pintype "passive"))
      (node (ref "T9") (pin "3") (pinfunction "D_3") (pintype "passive"))
    )
    (net (code "95") (name "Net-(OK4-A)") (class "Default")
      (node (ref "OK4") (pin "1") (pinfunction "A_1") (pintype "passive"))
      (node (ref "R42") (pin "1") (pinfunction "1_1") (pintype "passive"))
    )
    (net (code "96") (name "Net-(OK4-C)") (class "Default")
      (node (ref "OK4") (pin "2") (pinfunction "C_2") (pintype "passive"))
      (node (ref "T10") (pin "3") (pinfunction "D_3") (pintype "passive"))
    )
    (net (code "97") (name "Net-(OK5-A)") (class "Default")
      (node (ref "OK5") (pin "1") (pinfunction "A_1") (pintype "passive"))
      (node (ref "R43") (pin "1") (pinfunction "1_1") (pintype "passive"))
    )
    (net (code "98") (name "Net-(OK5-C)") (class "Default")
      (node (ref "OK5") (pin "2") (pinfunction "C_2") (pintype "passive"))
      (node (ref "T11") (pin "3") (pinfunction "D_3") (pintype "passive"))
    )
    (net (code "99") (name "Net-(OK6-A)") (class "Default")
      (node (ref "OK6") (pin "1") (pinfunction "A_1") (pintype "passive"))
      (node (ref "R44") (pin "1") (pinfunction "1_1") (pintype "passive"))
    )
    (net (code "100") (name "Net-(OK6-C)") (class "Default")
      (node (ref "OK6") (pin "2") (pinfunction "C_2") (pintype "passive"))
      (node (ref "T12") (pin "3") (pinfunction "D_3") (pintype "passive"))
    )
    (net (code "101") (name "Net-(Q11-G)") (class "Default")
      (node (ref "Q11") (pin "1") (pinfunction "G_1") (pintype "passive"))
      (node (ref "R70") (pin "1") (pinfunction "1_1") (pintype "passive"))
    )
    (net (code "102") (name "Net-(T1-D)") (class "Default")
      (node (ref "D22") (pin "C") (pinfunction "C_C") (pintype "passive"))
      (node (ref "T1") (pin "1") (pinfunction "D_1") (pintype "passive"))
    )
    (net (code "103") (name "Net-(T1-G)") (class "Default")
      (node (ref "D23") (pin "C") (pinfunction "C_C") (pintype "passive"))
      (node (ref "R11") (pin "1") (pinfunction "1_1") (pintype "passive"))
      (node (ref "T1") (pin "3") (pinfunction "G_3") (pintype "passive"))
    )
    (net (code "104") (name "Net-(T1-S)") (class "Default")
      (node (ref "C10") (pin "1") (pinfunction "1_1") (pintype "passive"))
      (node (ref "R37") (pin "2") (pinfunction "2_2") (pintype "passive"))
      (node (ref "R9") (pin "2") (pinfunction "2_2") (pintype "passive"))
      (node (ref "T1") (pin "2") (pinfunction "S_2") (pintype "passive"))
    )
    (net (code "105") (name "Net-(T3-D)") (class "Default")
      (node (ref "D28") (pin "C") (pinfunction "C_C") (pintype "passive"))
      (node (ref "T3") (pin "1") (pinfunction "D_1") (pintype "passive"))
    )
    (net (code "106") (name "Net-(T3-G)") (class "Default")
      (node (ref "D29") (pin "C") (pinfunction "C_C") (pintype "passive"))
      (node (ref "R15") (pin "1") (pinfunction "1_1") (pintype "passive"))
      (node (ref "T3") (pin "3") (pinfunction "G_3") (pintype "passive"))
    )
    (net (code "107") (name "Net-(T3-S)") (class "Default")
      (node (ref "C4") (pin "1") (pinfunction "1_1") (pintype "passive"))
      (node (ref "R14") (pin "2") (pinfunction "2_2") (pintype "passive"))
      (node (ref "R38") (pin "2") (pinfunction "2_2") (pintype "passive"))
      (node (ref "T3") (pin "2") (pinfunction "S_2") (pintype "passive"))
    )
    (net (code "108") (name "Net-(T5-D)") (class "Default")
      (node (ref "D34") (pin "C") (pinfunction "C_C") (pintype "passive"))
      (node (ref "T5") (pin "1") (pinfunction "D_1") (pintype "passive"))
    )
    (net (code "109") (name "Net-(T5-G)") (class "Default")
      (node (ref "D35") (pin "C") (pinfunction "C_C") (pintype "passive"))
      (node (ref "R21") (pin "1") (pinfunction "1_1") (pintype "passive"))
      (node (ref "T5") (pin "3") (pinfunction "G_3") (pintype "passive"))
    )
    (net (code "110") (name "Net-(T5-S)") (class "Default")
      (node (ref "C11") (pin "1") (pinfunction "1_1") (pintype "passive"))
      (node (ref "R20") (pin "2") (pinfunction "2_2") (pintype "passive"))
      (node (ref "R40") (pin "2") (pinfunction "2_2") (pintype "passive"))
      (node (ref "T5") (pin "2") (pinfunction "S_2") (pintype "passive"))
    )
    (net (code "111") (name "Net-(T7-D)") (class "Default")
      (node (ref "D40") (pin "C") (pinfunction "C_C") (pintype "passive"))
      (node (ref "T7") (pin "1") (pinfunction "D_1") (pintype "passive"))
    )
    (net (code "112") (name "Net-(T7-G)") (class "Default")
      (node (ref "D41") (pin "C") (pinfunction "C_C") (pintype "passive"))
      (node (ref "R28") (pin "1") (pinfunction "1_1") (pintype "passive"))
      (node (ref "T7") (pin "3") (pinfunction "G_3") (pintype "passive"))
    )
    (net (code "113") (name "Net-(T7-S)") (class "Default")
      (node (ref "C5") (pin "1") (pinfunction "1_1") (pintype "passive"))
      (node (ref "R27") (pin "2") (pinfunction "2_2") (pintype "passive"))
      (node (ref "R39") (pin "2") (pinfunction "2_2") (pintype "passive"))
      (node (ref "T7") (pin "2") (pinfunction "S_2") (pintype "passive"))
    )
    (net (code "114") (name "Net-(U1-IN)") (class "Default")
      (node (ref "C13") (pin "1") (pinfunction "1_1") (pintype "passive"))
      (node (ref "D5") (pin "C") (pinfunction "C_C") (pintype "passive"))
      (node (ref "F1") (pin "2") (pinfunction "2_2") (pintype "passive"))
      (node (ref "U1") (pin "2") (pinfunction "IN_2") (pintype "bidirectional"))
    )
    (net (code "115") (name "Net-(U6-A)") (class "Default")
      (node (ref "R69") (pin "1") (pinfunction "1_1") (pintype "passive"))
      (node (ref "U6") (pin "6") (pinfunction "A_6") (pintype "output"))
    )
    (net (code "116") (name "Net-(U6-B)") (class "Default")
      (node (ref "R68") (pin "1") (pinfunction "1_1") (pintype "passive"))
      (node (ref "U6") (pin "7") (pinfunction "B_7") (pintype "output"))
    )
    (net (code "117") (name "Net-(X2B-KL)") (class "Default")
      (node (ref "X2") (pin "10") (pinfunction "KL_10") (pintype "passive"))
      (node (ref "X2") (pin "9") (pinfunction "KL_9") (pintype "passive"))
    )
    (net (code "118") (name "unconnected-(IC1-SCK{slash}PB2-Pad7)") (class "Default")
      (node (ref "IC1") (pin "7") (pinfunction "SCK/PB2_7") (pintype "bidirectional"))
    )
    (net (code "119") (name "unconnected-(IC3-SCK{slash}PB2-Pad7)") (class "Default")
      (node (ref "IC3") (pin "7") (pinfunction "SCK/PB2_7") (pintype "bidirectional"))
    )
    (net (code "120") (name "unconnected-(IC5-SCK{slash}PB2-Pad7)") (class "Default")
      (node (ref "IC5") (pin "7") (pinfunction "SCK/PB2_7") (pintype "bidirectional"))
    )
    (net (code "121") (name "unconnected-(IC7-SCK{slash}PB2-Pad7)") (class "Default")
      (node (ref "IC7") (pin "7") (pinfunction "SCK/PB2_7") (pintype "bidirectional"))
    )
    (net (code "122") (name "unconnected-(K5-Pad6)") (class "Default")
      (node (ref "K5") (pin "6") (pinfunction "6_6") (pintype "passive"))
    )
    (net (code "123") (name "unconnected-(Q11-S-Pad2)") (class "Default")
      (node (ref "Q11") (pin "2") (pinfunction "S_2") (pintype "passive"))
    )
    (net (code "124") (name "unconnected-(U$4-PA0{slash}USART4_TX{slash}WKUP1{slash}ADC_IN0-Pad10)") (class "Default")
      (node (ref "U$4") (pin "10") (pinfunction "PA0/USART4_TX/WKUP1/ADC_IN0_10") (pintype "bidirectional"))
    )
    (net (code "125") (name "unconnected-(U$4-PA1{slash}ADC_IN1{slash}COMP1_INP{slash}USART4_RX-Pad11)") (class "Default")
      (node (ref "U$4") (pin "11") (pinfunction "PA1/ADC_IN1/COMP1_INP/USART4_RX_11") (pintype "bidirectional"))
    )
    (net (code "126") (name "unconnected-(U$4-PA2{slash}ADC_IN2{slash}WKUP4USART2_TX-Pad12)") (class "Default")
      (node (ref "U$4") (pin "12") (pinfunction "PA2/ADC_IN2/WKUP4USART2_TX_12") (pintype "bidirectional"))
    )
    (net (code "127") (name "unconnected-(U$4-PA3{slash}ADC_IN3{slash}COMP2_INP{slash}USART2_RX-Pad13)") (class "Default")
      (node (ref "U$4") (pin "13") (pinfunction "PA3/ADC_IN3/COMP2_INP/USART2_RX_13") (pintype "bidirectional"))
    )
    (net (code "128") (name "unconnected-(U$4-PA4{slash}ADC_IN4{slash}DAC_OUT1-Pad14)") (class "Default")
      (node (ref "U$4") (pin "14") (pinfunction "PA4/ADC_IN4/DAC_OUT1_14") (pintype "bidirectional"))
    )
    (net (code "129") (name "unconnected-(U$4-PA5{slash}ADC_IN5{slash}DAC_OUT2{slash}SPI1_SCK-Pad15)") (class "Default")
      (node (ref "U$4") (pin "15") (pinfunction "PA5/ADC_IN5/DAC_OUT2/SPI1_SCK_15") (pintype "bidirectional"))
    )
    (net (code "130") (name "unconnected-(U$4-PA6{slash}ADC_IN6{slash}SPI1_MISO{slash}TIM3_CH1-Pad16)") (class "Default")
      (node (ref "U$4") (pin "16") (pinfunction "PA6/ADC_IN6/SPI1_MISO/TIM3_CH1_16") (pintype "bidirectional"))
    )
    (net (code "131") (name "unconnected-(U$4-PA7{slash}ADC_IN7{slash}SPI1_MOSI{slash}TIM3_CH2-Pad17)") (class "Default")
      (node (ref "U$4") (pin "17") (pinfunction "PA7/ADC_IN7/SPI1_MOSI/TIM3_CH2_17") (pintype "bidirectional"))
    )
    (net (code "132") (name "unconnected-(U$4-PA12{slash}USB_DP{slash}CAN_TX-Pad33)") (class "Default")
      (node (ref "U$4") (pin "33") (pinfunction "PA12/USB_DP/CAN_TX_33") (pintype "bidirectional"))
    )
    (net (code "133") (name "unconnected-(U$4-PA15{slash}USART2_RX-Pad38)") (class "Default")
      (node (ref "U$4") (pin "38") (pinfunction "PA15/USART2_RX_38") (pintype "bidirectional"))
    )
    (net (code "134") (name "unconnected-(U$4-PB0{slash}ADC_IN8{slash}TIM3_CH3-Pad18)") (class "Default")
      (node (ref "U$4") (pin "18") (pinfunction "PB0/ADC_IN8/TIM3_CH3_18") (pintype "bidirectional"))
    )
    (net (code "135") (name "unconnected-(U$4-PB1{slash}ADC_IN9{slash}TIM3_CH4-Pad19)") (class "Default")
      (node (ref "U$4") (pin "19") (pinfunction "PB1/ADC_IN9/TIM3_CH4_19") (pintype "bidirectional"))
    )
    (net (code "136") (name "unconnected-(U$4-PB2-Pad20)") (class "Default")
      (node (ref "U$4") (pin "20") (pinfunction "PB2_20") (pintype "bidirectional"))
    )
    (net (code "137") (name "unconnected-(U$4-PB3{slash}SPI1_SCK{slash}TIM2_CH2-Pad39)") (class "Default")
      (node (ref "U$4") (pin "39") (pinfunction "PB3/SPI1_SCK/TIM2_CH2_39") (pintype "bidirectional"))
    )
    (net (code "138") (name "unconnected-(U$4-PB4{slash}SPI1_MISO{slash}TIM3_CH1-Pad40)") (class "Default")
      (node (ref "U$4") (pin "40") (pinfunction "PB4/SPI1_MISO/TIM3_CH1_40") (pintype "bidirectional"))
    )
    (net (code "139") (name "unconnected-(U$4-PB5{slash}WKUP6{slash}SPI1_MOSI{slash}TIM3_CH2-Pad41)") (class "Default")
      (node (ref "U$4") (pin "41") (pinfunction "PB5/WKUP6/SPI1_MOSI/TIM3_CH2_41") (pintype "bidirectional"))
    )
    (net (code "140") (name "unconnected-(U$4-PC13{slash}WKUP2{slash}RTC_TAMP1{slash}RTC_TS{slash}RTC_OUT-Pad2)") (class "Default")
      (node (ref "U$4") (pin "2") (pinfunction "PC13/WKUP2/RTC_TAMP1/RTC_TS/RTC_OUT_2") (pintype "bidirectional"))
    )
    (net (code "141") (name "unconnected-(U$4-PC14{slash}OSC32_IN-Pad3)") (class "Default")
      (node (ref "U$4") (pin "3") (pinfunction "PC14/OSC32_IN_3") (pintype "bidirectional"))
    )
    (net (code "142") (name "unconnected-(U$4-PC15{slash}OSC32_OUT-Pad4)") (class "Default")
      (node (ref "U$4") (pin "4") (pinfunction "PC15/OSC32_OUT_4") (pintype "bidirectional"))
    )
    (net (code "143") (name "unconnected-(U$4-PF0{slash}OSC_IN-Pad5)") (class "Default")
      (node (ref "U$4") (pin "5") (pinfunction "PF0/OSC_IN_5") (pintype "bidirectional"))
    )
    (net (code "144") (name "unconnected-(U$4-PF1{slash}OSC_OUT-Pad6)") (class "Default")
      (node (ref "U$4") (pin "6") (pinfunction "PF1/OSC_OUT_6") (pintype "bidirectional"))
    )
    (net (code "145") (name "unconnected-(U$4-VBATT(P1)-Pad1)") (class "Default")
      (node (ref "U$4") (pin "1") (pinfunction "VBATT(P1)_1") (pintype "bidirectional"))
    )
  )
)
